# OBCv4_23.net
KiCad netlist of a schematic drawn in EAGLE
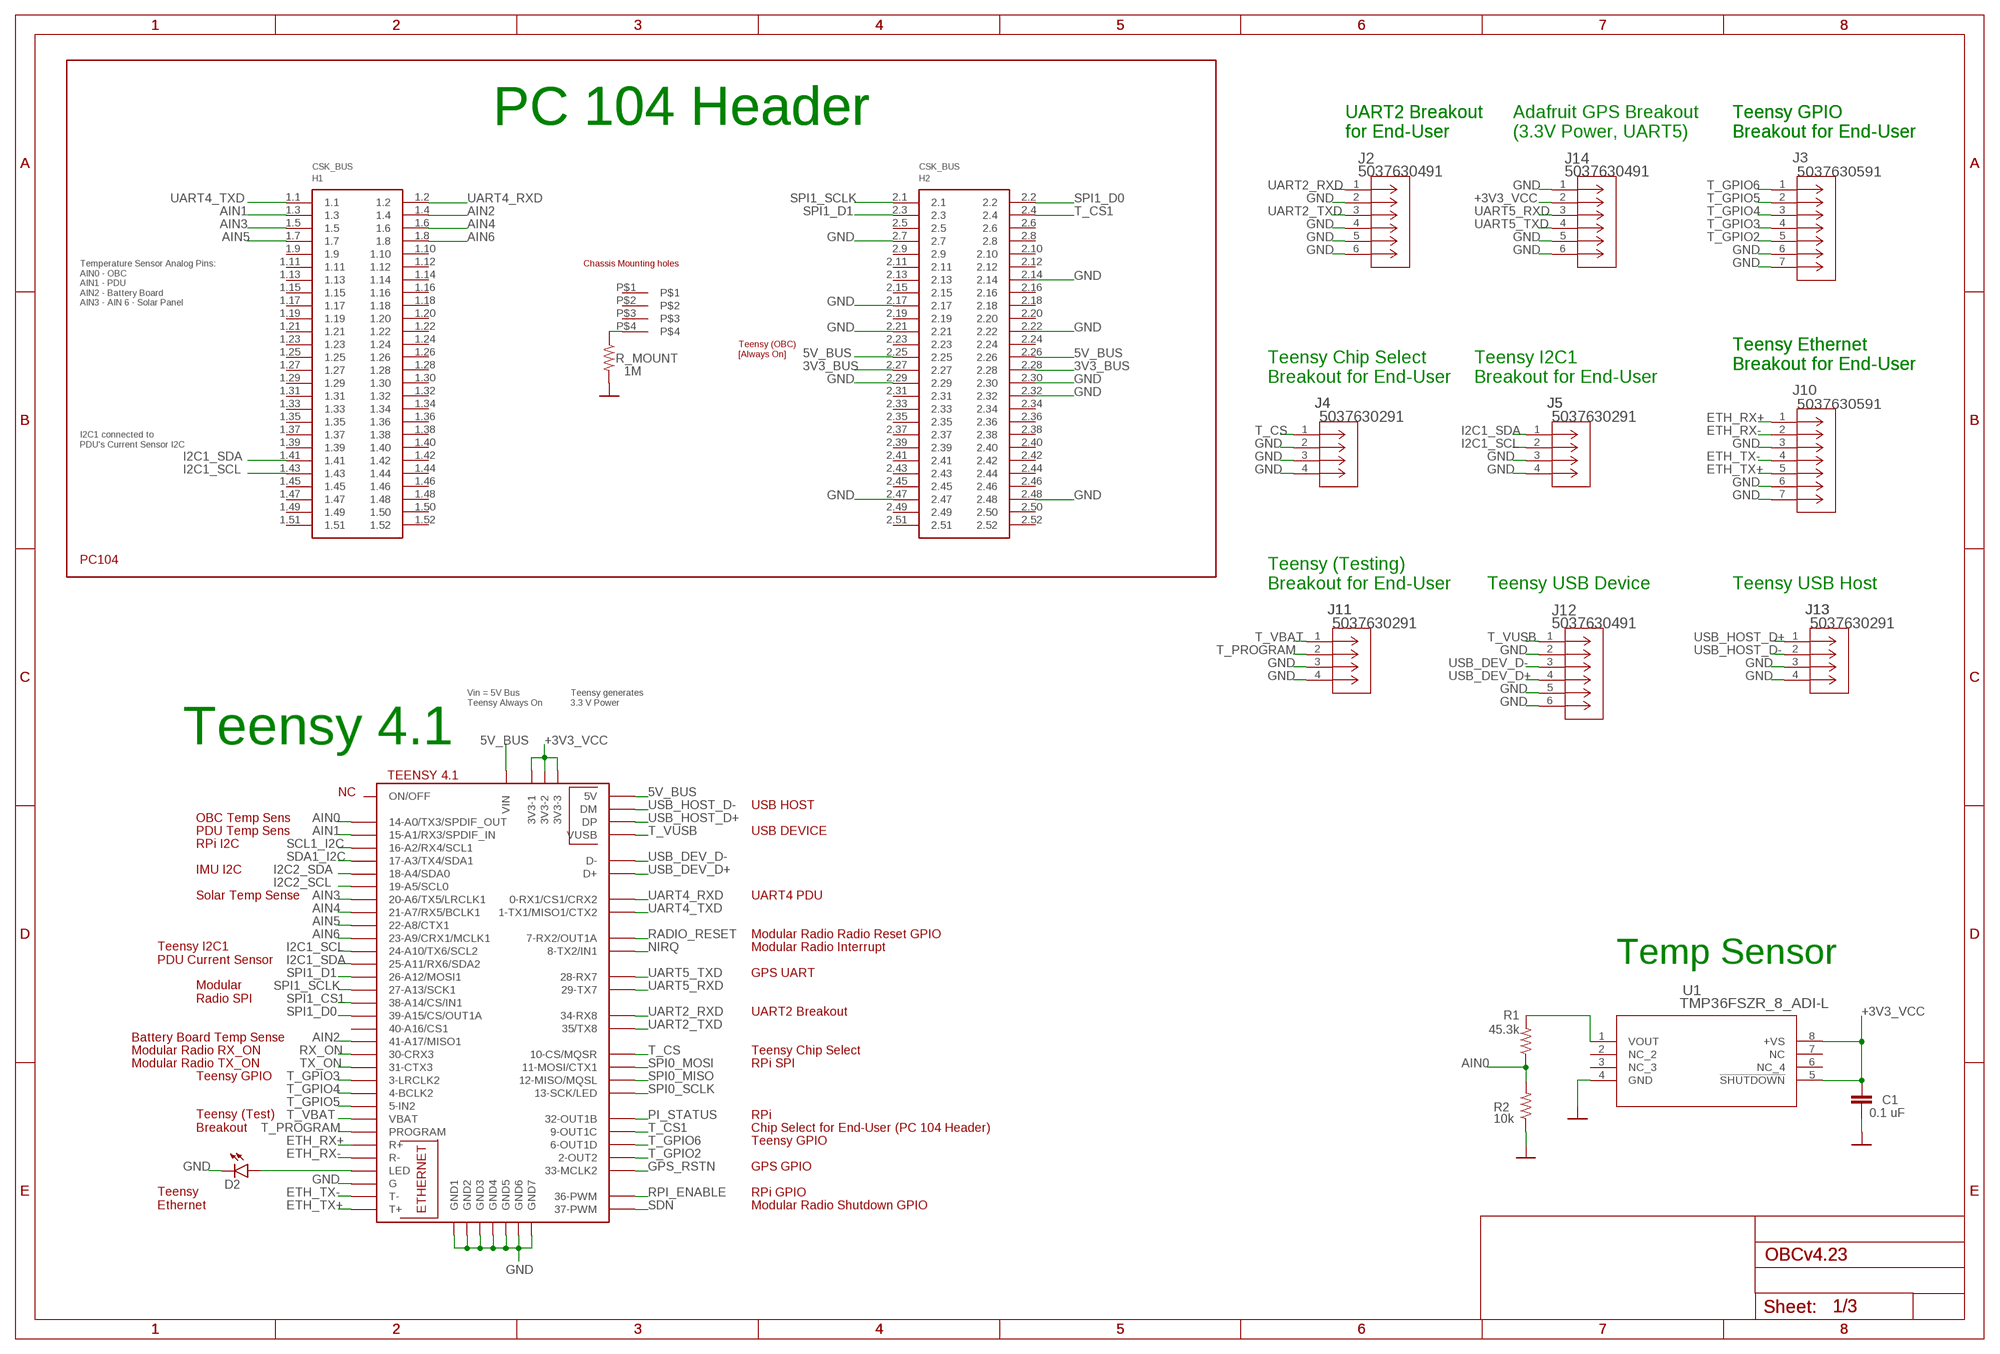
[diagram p0: schematic, sheet 1]
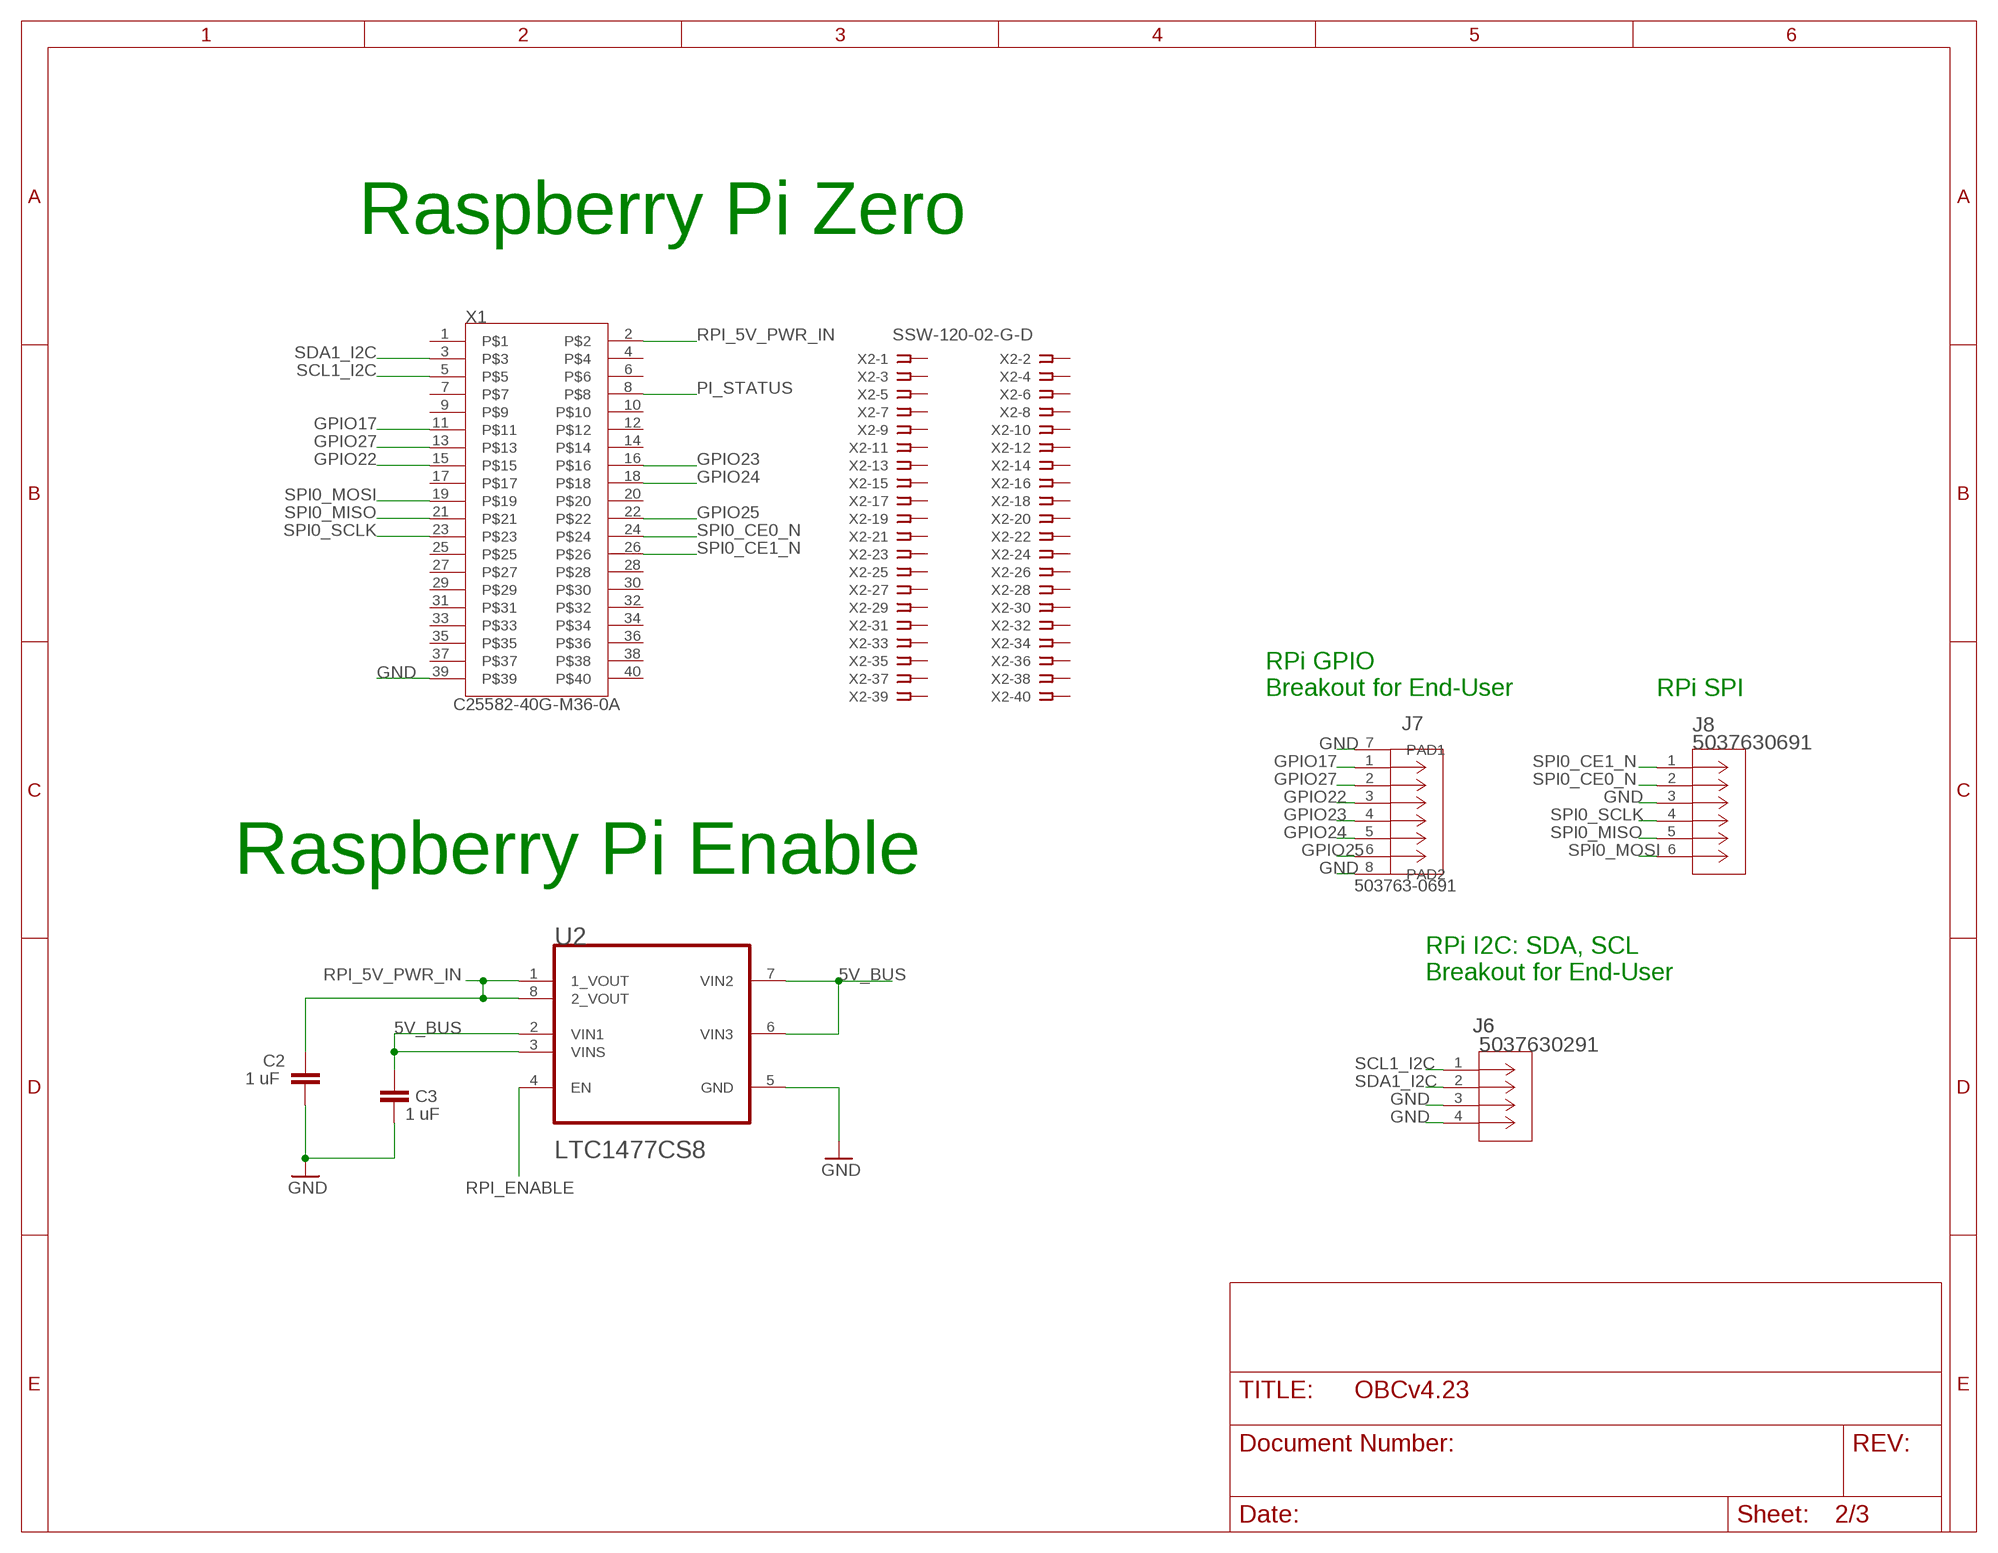
[diagram p1: schematic, sheet 2]
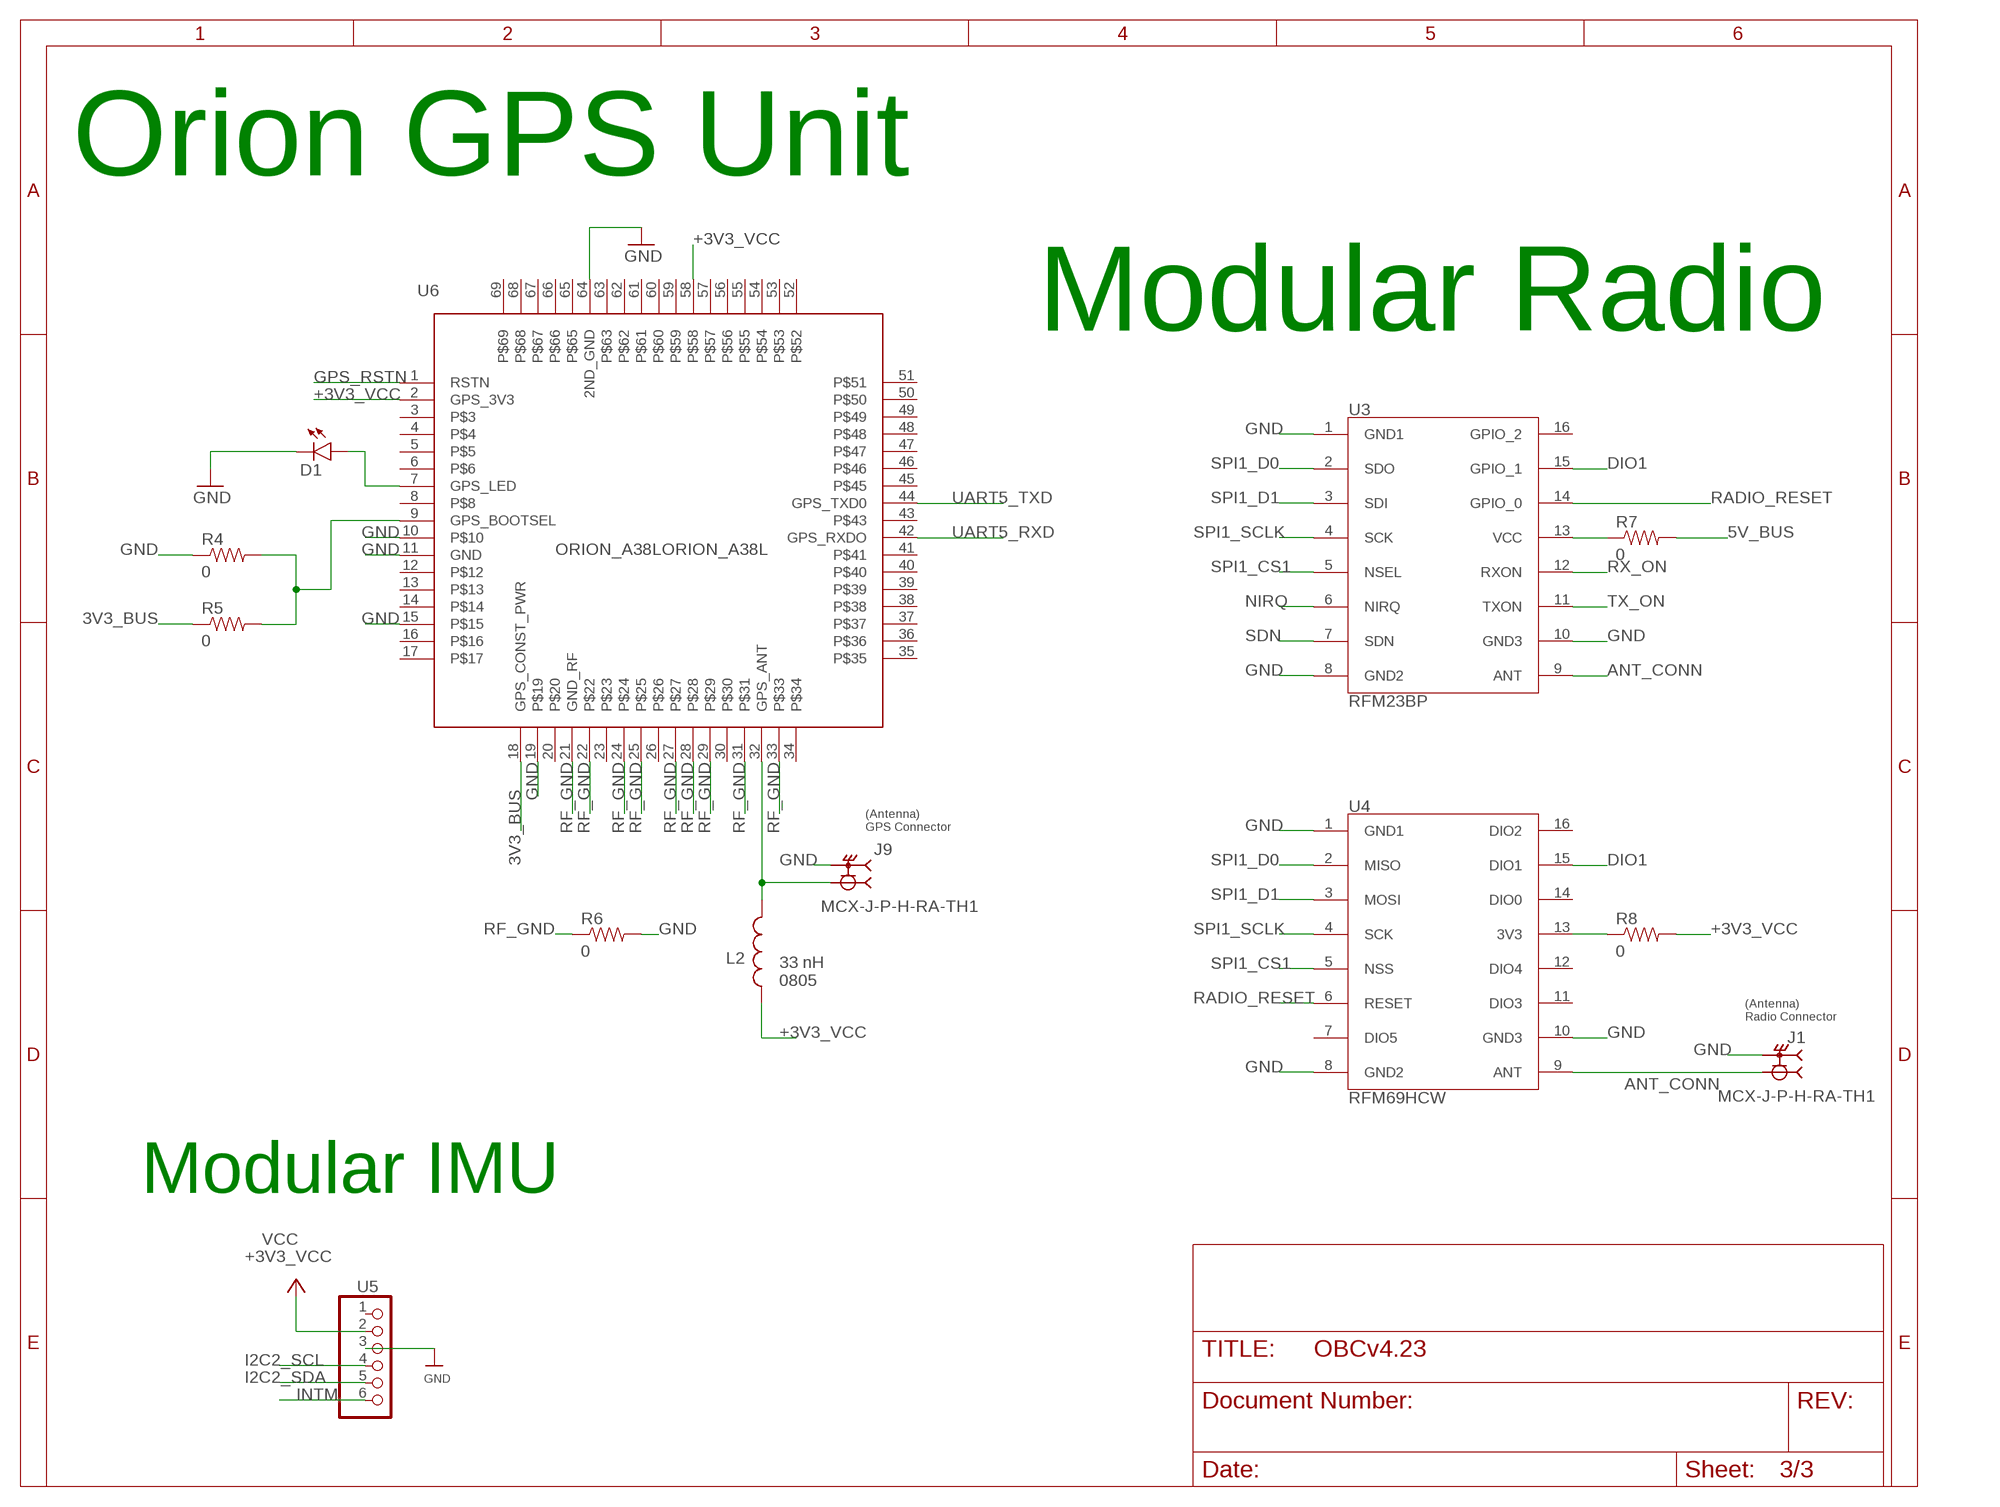
[diagram p2: schematic, sheet 3]

(export (version "E")
  (design (tool "Eeschema 10.0.6"))
  (components
    (comp (ref "D1")
      (value "LEDCHIP-LED0603")
      (footprint "eagle-import:CHIP-LED0603")
      (libsource (lib "eagle-import") (part "LEDCHIP-LED0603"))
    )
    (comp (ref "J1")
      (value "MCX-J-P-H-RA-TH1")
      (footprint "eagle-import:SAMTEC_MCX-J-P-H-RA-TH1")
      (fields (field (name "DIGI-KEY_PART_NUMBER") "SAM10607-ND") (field (name "MF") "Samtec"))
      (libsource (lib "eagle-import") (part "MCX-J-P-H-RA-TH1"))
    )
    (comp (ref "J9")
      (value "MCX-J-P-H-RA-TH1")
      (footprint "eagle-import:SAMTEC_MCX-J-P-H-RA-TH1")
      (fields (field (name "DIGI-KEY_PART_NUMBER") "SAM10607-ND") (field (name "MF") "Samtec"))
      (libsource (lib "eagle-import") (part "MCX-J-P-H-RA-TH1"))
    )
    (comp (ref "L2")
      (value "AIMC-0805-2N2S-T")
      (footprint "eagle-import:INDC2012X105N")
      (fields (field (name "DIGI-KEY_PART_NUMBER") "535-11562-1-ND") (field (name "MF") "Abracon"))
      (libsource (lib "eagle-import") (part "AIMC-0805-2N2S-T"))
    )
    (comp (ref "R4")
      (value "0")
      (footprint "eagle-import:0805")
      (libsource (lib "eagle-import") (part "RESISTOR0805-RES"))
    )
    (comp (ref "R5")
      (value "0")
      (footprint "eagle-import:0805")
      (libsource (lib "eagle-import") (part "RESISTOR0805-RES"))
    )
    (comp (ref "R6")
      (value "0")
      (footprint "eagle-import:0805")
      (libsource (lib "eagle-import") (part "RESISTOR0805-RES"))
    )
    (comp (ref "R7")
      (value "0")
      (footprint "eagle-import:1206")
      (libsource (lib "eagle-import") (part "RESISTOR1206"))
    )
    (comp (ref "R8")
      (value "0")
      (footprint "eagle-import:1206")
      (libsource (lib "eagle-import") (part "RESISTOR1206"))
    )
    (comp (ref "U3")
      (value "RFM23BP")
      (footprint "eagle-import:RFM23BP")
      (libsource (lib "eagle-import") (part "RFM23BP"))
    )
    (comp (ref "U4")
      (value "RFM69HCW")
      (footprint "eagle-import:RFM69HCW")
      (libsource (lib "eagle-import") (part "RFM69HCW"))
    )
    (comp (ref "U5")
      (value "HEADER-1X670MIL")
      (footprint "eagle-import:1X06_ROUND_70")
      (libsource (lib "eagle-import") (part "HEADER-1X670MIL"))
    )
    (comp (ref "U6")
      (value "ORION_A38LORION_A38L")
      (footprint "eagle-import:ORION_A38L")
      (libsource (lib "eagle-import") (part "ORION_A38LORION_A38L"))
    )
    (comp (ref "C1")
      (value "0.1 uF")
      (footprint "eagle-import:0805")
      (libsource (lib "eagle-import") (part "CAP0805"))
    )
    (comp (ref "D2")
      (value "LEDCHIP-LED0603")
      (footprint "eagle-import:CHIP-LED0603")
      (libsource (lib "eagle-import") (part "LEDCHIP-LED0603"))
    )
    (comp (ref "H1")
      (value "PC104_WCONN")
      (footprint "eagle-import:PC104_WCONN")
      (libsource (lib "eagle-import") (part "PC104_WCONN"))
    )
    (comp (ref "J2")
      (value "5037630491")
      (footprint "eagle-import:CON_5037630491")
      (fields (field (name "COPYRIGHT") "Copyright (C) 2018 Accelerated Designs. All rights reserved"))
      (libsource (lib "eagle-import") (part "5037630491"))
    )
    (comp (ref "J3")
      (value "5037630591")
      (footprint "eagle-import:CON_5037630591")
      (fields (field (name "COPYRIGHT") "Copyright (C) 2021 Ultra Librarian. All rights reserved."))
      (libsource (lib "eagle-import") (part "5037630591"))
    )
    (comp (ref "J4")
      (value "5037630291")
      (footprint "eagle-import:CON_5037630291")
      (fields (field (name "COPYRIGHT") "Copyright (C) 2018 Accelerated Designs. All rights reserved"))
      (libsource (lib "eagle-import") (part "5037630291"))
    )
    (comp (ref "J5")
      (value "5037630291")
      (footprint "eagle-import:CON_5037630291")
      (fields (field (name "COPYRIGHT") "Copyright (C) 2018 Accelerated Designs. All rights reserved"))
      (libsource (lib "eagle-import") (part "5037630291"))
    )
    (comp (ref "J10")
      (value "5037630591")
      (footprint "eagle-import:CON_5037630591")
      (fields (field (name "COPYRIGHT") "Copyright (C) 2021 Ultra Librarian. All rights reserved."))
      (libsource (lib "eagle-import") (part "5037630591"))
    )
    (comp (ref "J11")
      (value "5037630291")
      (footprint "eagle-import:CON_5037630291")
      (fields (field (name "COPYRIGHT") "Copyright (C) 2018 Accelerated Designs. All rights reserved"))
      (libsource (lib "eagle-import") (part "5037630291"))
    )
    (comp (ref "J12")
      (value "5037630491")
      (footprint "eagle-import:CON_5037630491")
      (fields (field (name "COPYRIGHT") "Copyright (C) 2018 Accelerated Designs. All rights reserved"))
      (libsource (lib "eagle-import") (part "5037630491"))
    )
    (comp (ref "J13")
      (value "5037630291")
      (footprint "eagle-import:CON_5037630291")
      (fields (field (name "COPYRIGHT") "Copyright (C) 2018 Accelerated Designs. All rights reserved"))
      (libsource (lib "eagle-import") (part "5037630291"))
    )
    (comp (ref "J14")
      (value "5037630491")
      (footprint "eagle-import:CON_5037630491")
      (fields (field (name "COPYRIGHT") "Copyright (C) 2018 Accelerated Designs. All rights reserved"))
      (libsource (lib "eagle-import") (part "5037630491"))
    )
    (comp (ref "R1")
      (value "45.3k")
      (footprint "eagle-import:0805")
      (libsource (lib "eagle-import") (part "RESISTOR0805-RES"))
    )
    (comp (ref "R2")
      (value "10k")
      (footprint "eagle-import:0805")
      (libsource (lib "eagle-import") (part "RESISTOR0805-RES"))
    )
    (comp (ref "R_MOUNT")
      (value "1M")
      (footprint "eagle-import:0805")
      (libsource (lib "eagle-import") (part "RESISTOR0805-RES"))
    )
    (comp (ref "U$1")
      (value "TEENSY41TEENSY")
      (footprint "eagle-import:TEENSY41")
      (libsource (lib "eagle-import") (part "TEENSY41TEENSY"))
    )
    (comp (ref "U1")
      (value "TMP36FSZR_8_ADI-L")
      (footprint "eagle-import:R_8_ADI-L")
      (fields
        (field (name "MANUFACTURER_PART_NUMBER") "TMP36FSZ")
        (field (name "COPYRIGHT") "Copyright (C) 2021 Ultra Librarian. All rights reserved.")
      )
      (libsource (lib "eagle-import") (part "TMP36FSZR_8_ADI-L"))
    )
    (comp (ref "C2")
      (value "1 uF")
      (footprint "eagle-import:0805")
      (libsource (lib "eagle-import") (part "CAP0805"))
    )
    (comp (ref "C3")
      (value "1 uF")
      (footprint "eagle-import:0805")
      (libsource (lib "eagle-import") (part "CAP0805"))
    )
    (comp (ref "J6")
      (value "5037630291")
      (footprint "eagle-import:CON_5037630291")
      (fields (field (name "COPYRIGHT") "Copyright (C) 2018 Accelerated Designs. All rights reserved"))
      (libsource (lib "eagle-import") (part "5037630291"))
    )
    (comp (ref "J7")
      (value "503763-0691")
      (footprint "eagle-import:CONN_503763-0691_MOL")
      (fields (field (name "COPYRIGHT") "Copyright (C) 2018 Accelerated Designs. All rights reserved"))
      (libsource (lib "eagle-import") (part "503763-0691"))
    )
    (comp (ref "J8")
      (value "5037630691")
      (footprint "eagle-import:CONN_503763-0691_MOL")
      (fields
        (field (name "MANUFACTURER_PART_NUMBER") "503763-0691")
        (field (name "COPYRIGHT") "Copyright (C) 2018 Accelerated Designs. All rights reserved")
      )
      (libsource (lib "eagle-import") (part "5037630691"))
    )
    (comp (ref "U2")
      (value "LTC1477CS8LINEAR_TECHNOLOGY_LTC1477CS8_0_2")
      (footprint "eagle-import:LINEAR_TECHNOLOGY_LTC1477CS8_2")
      (fields (field (name "MF") "Linear Technology") (field (name "MPN") "LTC1477CS8"))
      (libsource (lib "eagle-import") (part "LTC1477CS8LINEAR_TECHNOLOGY_LTC1477CS8_0_2"))
    )
    (comp (ref "X1")
      (value "C25582-40G-M36-0A")
      (footprint "eagle-import:ADAFRUIT_C25582-40G-M36-0A_0")
      (libsource (lib "eagle-import") (part "C25582-40G-M36-0A"))
    )
    (comp (ref "X2")
      (value "SSW-120-02-G-D")
      (footprint "eagle-import:SSW-120-02-G-D")
      (fields (field (name "MF") "Samtec Inc."))
      (libsource (lib "eagle-import") (part "SSW-120-02-G-D"))
    )
  )
  (nets
    (net (code "1") (name "+3V3_VCC") (class "Default")
      (node (ref "C1") (pin "1") (pinfunction "1_1") (pintype "passive"))
      (node (ref "J14") (pin "2") (pinfunction "2_2") (pintype "passive"))
      (node (ref "L2") (pin "1") (pinfunction "1_1") (pintype "passive"))
      (node (ref "R8") (pin "2") (pinfunction "2_2") (pintype "passive"))
      (node (ref "U$1") (pin "3V3-1") (pinfunction "3V3-1_3V3-1") (pintype "bidirectional"))
      (node (ref "U$1") (pin "3V3-2") (pinfunction "3V3-2_3V3-2") (pintype "bidirectional"))
      (node (ref "U$1") (pin "3V3-3") (pinfunction "3V3-3_3V3-3") (pintype "bidirectional"))
      (node (ref "U1") (pin "5") (pinfunction "~{SHUTDOWN}_5") (pintype "passive"))
      (node (ref "U1") (pin "8") (pinfunction "+VS_8") (pintype "power_in"))
      (node (ref "U5") (pin "2") (pinfunction "2_2") (pintype "passive"))
      (node (ref "U6") (pin "2") (pinfunction "GPS_3V3_2") (pintype "bidirectional"))
      (node (ref "U6") (pin "58") (pinfunction "P$58_58") (pintype "bidirectional"))
    )
    (net (code "2") (name "3V3_BUS") (class "Default")
      (node (ref "H1") (pin "2.27") (pinfunction "2.27_2.27") (pintype "bidirectional"))
      (node (ref "H1") (pin "2.28") (pinfunction "2.28_2.28") (pintype "bidirectional"))
      (node (ref "R5") (pin "1") (pinfunction "1_1") (pintype "passive"))
      (node (ref "U6") (pin "18") (pinfunction "GPS_CONST_PWR_18") (pintype "bidirectional"))
    )
    (net (code "3") (name "5V_BUS") (class "Default")
      (node (ref "C3") (pin "1") (pinfunction "1_1") (pintype "passive"))
      (node (ref "H1") (pin "2.25") (pinfunction "2.25_2.25") (pintype "bidirectional"))
      (node (ref "H1") (pin "2.26") (pinfunction "2.26_2.26") (pintype "bidirectional"))
      (node (ref "R7") (pin "2") (pinfunction "2_2") (pintype "passive"))
      (node (ref "U$1") (pin "+5V") (pinfunction "5V_+5V") (pintype "bidirectional"))
      (node (ref "U$1") (pin "VIN") (pinfunction "VIN_VIN") (pintype "bidirectional"))
      (node (ref "U2") (pin "2") (pinfunction "VIN1_2") (pintype "power_in"))
      (node (ref "U2") (pin "3") (pinfunction "VINS_3") (pintype "power_in"))
      (node (ref "U2") (pin "6") (pinfunction "VIN3_6") (pintype "power_in"))
      (node (ref "U2") (pin "7") (pinfunction "VIN2_7") (pintype "power_in"))
    )
    (net (code "4") (name "AIN0") (class "Default")
      (node (ref "R1") (pin "1") (pinfunction "1_1") (pintype "passive"))
      (node (ref "R2") (pin "2") (pinfunction "2_2") (pintype "passive"))
      (node (ref "U$1") (pin "14-A0/TX3/SPDIF_OUT") (pinfunction "14-A0/TX3/SPDIF_OUT_14-A0/TX3/SPDIF_OUT") (pintype "bidirectional"))
    )
    (net (code "5") (name "AIN1") (class "Default")
      (node (ref "H1") (pin "1.3") (pinfunction "1.3_1.3") (pintype "bidirectional"))
      (node (ref "U$1") (pin "15-A1/RX3/SPDIF_IN") (pinfunction "15-A1/RX3/SPDIF_IN_15-A1/RX3/SPDIF_IN") (pintype "bidirectional"))
    )
    (net (code "6") (name "AIN2") (class "Default")
      (node (ref "H1") (pin "1.4") (pinfunction "1.4_1.4") (pintype "bidirectional"))
      (node (ref "U$1") (pin "41-A17/MISO1") (pinfunction "41-A17/MISO1_41-A17/MISO1") (pintype "bidirectional"))
    )
    (net (code "7") (name "AIN3") (class "Default")
      (node (ref "H1") (pin "1.5") (pinfunction "1.5_1.5") (pintype "bidirectional"))
      (node (ref "U$1") (pin "20-A6/TX5/LRCLK1") (pinfunction "20-A6/TX5/LRCLK1_20-A6/TX5/LRCLK1") (pintype "bidirectional"))
    )
    (net (code "8") (name "AIN4") (class "Default")
      (node (ref "H1") (pin "1.6") (pinfunction "1.6_1.6") (pintype "bidirectional"))
      (node (ref "U$1") (pin "21-A7/RX5/BCLK1") (pinfunction "21-A7/RX5/BCLK1_21-A7/RX5/BCLK1") (pintype "bidirectional"))
    )
    (net (code "9") (name "AIN5") (class "Default")
      (node (ref "H1") (pin "1.7") (pinfunction "1.7_1.7") (pintype "bidirectional"))
      (node (ref "U$1") (pin "22-A8/CTX1") (pinfunction "22-A8/CTX1_22-A8/CTX1") (pintype "bidirectional"))
    )
    (net (code "10") (name "AIN6") (class "Default")
      (node (ref "H1") (pin "1.8") (pinfunction "1.8_1.8") (pintype "bidirectional"))
      (node (ref "U$1") (pin "23-A9/CRX1/MCLK1") (pinfunction "23-A9/CRX1/MCLK1_23-A9/CRX1/MCLK1") (pintype "bidirectional"))
    )
    (net (code "11") (name "ANT_CONN") (class "Default")
      (node (ref "J1") (pin "1") (pinfunction "1_1") (pintype "passive"))
      (node (ref "U3") (pin "9") (pinfunction "ANT_9") (pintype "bidirectional"))
      (node (ref "U4") (pin "9") (pinfunction "ANT_9") (pintype "bidirectional"))
    )
    (net (code "12") (name "DIO1") (class "Default")
      (node (ref "U3") (pin "15") (pinfunction "GPIO_1_15") (pintype "bidirectional"))
      (node (ref "U4") (pin "15") (pinfunction "DIO1_15") (pintype "bidirectional"))
    )
    (net (code "13") (name "ETH_RX+") (class "Default")
      (node (ref "J10") (pin "1") (pinfunction "1_1") (pintype "passive"))
      (node (ref "U$1") (pin "R+") (pinfunction "R+_R+") (pintype "bidirectional"))
    )
    (net (code "14") (name "ETH_RX-") (class "Default")
      (node (ref "J10") (pin "2") (pinfunction "2_2") (pintype "passive"))
      (node (ref "U$1") (pin "R-") (pinfunction "R-_R-") (pintype "bidirectional"))
    )
    (net (code "15") (name "ETH_TX+") (class "Default")
      (node (ref "J10") (pin "5") (pinfunction "5_5") (pintype "passive"))
      (node (ref "U$1") (pin "T+") (pinfunction "T+_T+") (pintype "bidirectional"))
    )
    (net (code "16") (name "ETH_TX-") (class "Default")
      (node (ref "J10") (pin "4") (pinfunction "4_4") (pintype "passive"))
      (node (ref "U$1") (pin "T-") (pinfunction "T-_T-") (pintype "bidirectional"))
    )
    (net (code "17") (name "GND") (class "Default")
      (node (ref "C1") (pin "2") (pinfunction "2_2") (pintype "passive"))
      (node (ref "C2") (pin "2") (pinfunction "2_2") (pintype "passive"))
      (node (ref "C3") (pin "2") (pinfunction "2_2") (pintype "passive"))
      (node (ref "D1") (pin "C") (pinfunction "C_C") (pintype "passive"))
      (node (ref "D2") (pin "C") (pinfunction "C_C") (pintype "passive"))
      (node (ref "H1") (pin "2.14") (pinfunction "2.14_2.14") (pintype "bidirectional"))
      (node (ref "H1") (pin "2.17") (pinfunction "2.17_2.17") (pintype "bidirectional"))
      (node (ref "H1") (pin "2.21") (pinfunction "2.21_2.21") (pintype "bidirectional"))
      (node (ref "H1") (pin "2.22") (pinfunction "2.22_2.22") (pintype "bidirectional"))
      (node (ref "H1") (pin "2.29") (pinfunction "2.29_2.29") (pintype "bidirectional"))
      (node (ref "H1") (pin "2.30") (pinfunction "2.30_2.30") (pintype "bidirectional"))
      (node (ref "H1") (pin "2.32") (pinfunction "2.32_2.32") (pintype "bidirectional"))
      (node (ref "H1") (pin "2.47") (pinfunction "2.47_2.47") (pintype "bidirectional"))
      (node (ref "H1") (pin "2.48") (pinfunction "2.48_2.48") (pintype "bidirectional"))
      (node (ref "H1") (pin "2.7") (pinfunction "2.7_2.7") (pintype "bidirectional"))
      (node (ref "J1") (pin "S1") (pinfunction "2_S1") (pintype "passive"))
      (node (ref "J1") (pin "S2") (pinfunction "2_S2") (pintype "passive"))
      (node (ref "J1") (pin "S3") (pinfunction "2_S3") (pintype "passive"))
      (node (ref "J1") (pin "S4") (pinfunction "2_S4") (pintype "passive"))
      (node (ref "J10") (pin "3") (pinfunction "3_3") (pintype "passive"))
      (node (ref "J10") (pin "6") (pinfunction "6_6") (pintype "passive"))
      (node (ref "J10") (pin "7") (pinfunction "7_7") (pintype "passive"))
      (node (ref "J11") (pin "3") (pinfunction "3_3") (pintype "passive"))
      (node (ref "J11") (pin "4") (pinfunction "4_4") (pintype "passive"))
      (node (ref "J12") (pin "2") (pinfunction "2_2") (pintype "passive"))
      (node (ref "J12") (pin "5") (pinfunction "5_5") (pintype "passive"))
      (node (ref "J12") (pin "6") (pinfunction "6_6") (pintype "passive"))
      (node (ref "J13") (pin "3") (pinfunction "3_3") (pintype "passive"))
      (node (ref "J13") (pin "4") (pinfunction "4_4") (pintype "passive"))
      (node (ref "J14") (pin "1") (pinfunction "1_1") (pintype "passive"))
      (node (ref "J14") (pin "5") (pinfunction "5_5") (pintype "passive"))
      (node (ref "J14") (pin "6") (pinfunction "6_6") (pintype "passive"))
      (node (ref "J2") (pin "2") (pinfunction "2_2") (pintype "passive"))
      (node (ref "J2") (pin "4") (pinfunction "4_4") (pintype "passive"))
      (node (ref "J2") (pin "5") (pinfunction "5_5") (pintype "passive"))
      (node (ref "J2") (pin "6") (pinfunction "6_6") (pintype "passive"))
      (node (ref "J3") (pin "6") (pinfunction "6_6") (pintype "passive"))
      (node (ref "J3") (pin "7") (pinfunction "7_7") (pintype "passive"))
      (node (ref "J4") (pin "2") (pinfunction "2_2") (pintype "passive"))
      (node (ref "J4") (pin "3") (pinfunction "3_3") (pintype "passive"))
      (node (ref "J4") (pin "4") (pinfunction "4_4") (pintype "passive"))
      (node (ref "J5") (pin "3") (pinfunction "3_3") (pintype "passive"))
      (node (ref "J5") (pin "4") (pinfunction "4_4") (pintype "passive"))
      (node (ref "J6") (pin "3") (pinfunction "3_3") (pintype "passive"))
      (node (ref "J6") (pin "4") (pinfunction "4_4") (pintype "passive"))
      (node (ref "J7") (pin "7") (pinfunction "PAD1_7") (pintype "bidirectional"))
      (node (ref "J7") (pin "8") (pinfunction "PAD2_8") (pintype "bidirectional"))
      (node (ref "J8") (pin "3") (pinfunction "3_3") (pintype "passive"))
      (node (ref "J9") (pin "S1") (pinfunction "2_S1") (pintype "passive"))
      (node (ref "J9") (pin "S2") (pinfunction "2_S2") (pintype "passive"))
      (node (ref "J9") (pin "S3") (pinfunction "2_S3") (pintype "passive"))
      (node (ref "J9") (pin "S4") (pinfunction "2_S4") (pintype "passive"))
      (node (ref "R2") (pin "1") (pinfunction "1_1") (pintype "passive"))
      (node (ref "R4") (pin "1") (pinfunction "1_1") (pintype "passive"))
      (node (ref "R6") (pin "2") (pinfunction "2_2") (pintype "passive"))
      (node (ref "R_MOUNT") (pin "2") (pinfunction "2_2") (pintype "passive"))
      (node (ref "U$1") (pin "G") (pinfunction "G_G") (pintype "bidirectional"))
      (node (ref "U$1") (pin "GND") (pinfunction "GND7_GND") (pintype "bidirectional"))
      (node (ref "U$1") (pin "GND1") (pinfunction "GND1_GND1") (pintype "bidirectional"))
      (node (ref "U$1") (pin "GND2") (pinfunction "GND2_GND2") (pintype "bidirectional"))
      (node (ref "U$1") (pin "GND3") (pinfunction "GND3_GND3") (pintype "bidirectional"))
      (node (ref "U$1") (pin "GND4") (pinfunction "GND4_GND4") (pintype "bidirectional"))
      (node (ref "U$1") (pin "GND5") (pinfunction "GND5_GND5") (pintype "bidirectional"))
      (node (ref "U$1") (pin "GND6") (pinfunction "GND6_GND6") (pintype "bidirectional"))
      (node (ref "U1") (pin "4") (pinfunction "GND_4") (pintype "passive"))
      (node (ref "U2") (pin "5") (pinfunction "GND_5") (pintype "power_in"))
      (node (ref "U3") (pin "1") (pinfunction "GND1_1") (pintype "bidirectional"))
      (node (ref "U3") (pin "10") (pinfunction "GND3_10") (pintype "bidirectional"))
      (node (ref "U3") (pin "8") (pinfunction "GND2_8") (pintype "bidirectional"))
      (node (ref "U4") (pin "1") (pinfunction "GND1_1") (pintype "bidirectional"))
      (node (ref "U4") (pin "10") (pinfunction "GND3_10") (pintype "bidirectional"))
      (node (ref "U4") (pin "8") (pinfunction "GND2_8") (pintype "bidirectional"))
      (node (ref "U5") (pin "3") (pinfunction "3_3") (pintype "passive"))
      (node (ref "U6") (pin "10") (pinfunction "P$10_10") (pintype "bidirectional"))
      (node (ref "U6") (pin "11") (pinfunction "GND_11") (pintype "bidirectional"))
      (node (ref "U6") (pin "15") (pinfunction "P$15_15") (pintype "bidirectional"))
      (node (ref "U6") (pin "19") (pinfunction "P$19_19") (pintype "bidirectional"))
      (node (ref "U6") (pin "64") (pinfunction "2ND_GND_64") (pintype "bidirectional"))
      (node (ref "X1") (pin "39") (pinfunction "P$39_39") (pintype "bidirectional"))
    )
    (net (code "18") (name "GPIO17") (class "Default")
      (node (ref "J7") (pin "1") (pinfunction "1_1") (pintype "passive"))
      (node (ref "X1") (pin "11") (pinfunction "P$11_11") (pintype "bidirectional"))
    )
    (net (code "19") (name "GPIO22") (class "Default")
      (node (ref "J7") (pin "3") (pinfunction "3_3") (pintype "passive"))
      (node (ref "X1") (pin "15") (pinfunction "P$15_15") (pintype "bidirectional"))
    )
    (net (code "20") (name "GPIO23") (class "Default")
      (node (ref "J7") (pin "4") (pinfunction "4_4") (pintype "passive"))
      (node (ref "X1") (pin "16") (pinfunction "P$16_16") (pintype "bidirectional"))
    )
    (net (code "21") (name "GPIO24") (class "Default")
      (node (ref "J7") (pin "5") (pinfunction "5_5") (pintype "passive"))
      (node (ref "X1") (pin "18") (pinfunction "P$18_18") (pintype "bidirectional"))
    )
    (net (code "22") (name "GPIO25") (class "Default")
      (node (ref "J7") (pin "6") (pinfunction "6_6") (pintype "passive"))
      (node (ref "X1") (pin "22") (pinfunction "P$22_22") (pintype "bidirectional"))
    )
    (net (code "23") (name "GPIO27") (class "Default")
      (node (ref "J7") (pin "2") (pinfunction "2_2") (pintype "passive"))
      (node (ref "X1") (pin "13") (pinfunction "P$13_13") (pintype "bidirectional"))
    )
    (net (code "24") (name "GPS_RSTN") (class "Default")
      (node (ref "U$1") (pin "33-MCLK2") (pinfunction "33-MCLK2_33-MCLK2") (pintype "bidirectional"))
      (node (ref "U6") (pin "1") (pinfunction "RSTN_1") (pintype "bidirectional"))
    )
    (net (code "25") (name "I2C1_SCL") (class "Default")
      (node (ref "H1") (pin "1.43") (pinfunction "1.43_1.43") (pintype "bidirectional"))
      (node (ref "J5") (pin "2") (pinfunction "2_2") (pintype "passive"))
      (node (ref "U$1") (pin "24-A10/TX6/SCL2") (pinfunction "24-A10/TX6/SCL2_24-A10/TX6/SCL2") (pintype "bidirectional"))
    )
    (net (code "26") (name "I2C1_SDA") (class "Default")
      (node (ref "H1") (pin "1.41") (pinfunction "1.41_1.41") (pintype "bidirectional"))
      (node (ref "J5") (pin "1") (pinfunction "1_1") (pintype "passive"))
      (node (ref "U$1") (pin "25-A11/RX6/SDA2") (pinfunction "25-A11/RX6/SDA2_25-A11/RX6/SDA2") (pintype "bidirectional"))
    )
    (net (code "27") (name "I2C2_SCL") (class "Default")
      (node (ref "U$1") (pin "19-A5/SCL0") (pinfunction "19-A5/SCL0_19-A5/SCL0") (pintype "bidirectional"))
      (node (ref "U5") (pin "4") (pinfunction "4_4") (pintype "passive"))
    )
    (net (code "28") (name "I2C2_SDA") (class "Default")
      (node (ref "U$1") (pin "18-A4/SDA0") (pinfunction "18-A4/SDA0_18-A4/SDA0") (pintype "bidirectional"))
      (node (ref "U5") (pin "5") (pinfunction "5_5") (pintype "passive"))
    )
    (net (code "29") (name "INTM") (class "Default")
      (node (ref "U5") (pin "6") (pinfunction "6_6") (pintype "passive"))
    )
    (net (code "30") (name "NIRQ") (class "Default")
      (node (ref "U$1") (pin "8-TX2/IN1") (pinfunction "8-TX2/IN1_8-TX2/IN1") (pintype "bidirectional"))
      (node (ref "U3") (pin "6") (pinfunction "NIRQ_6") (pintype "bidirectional"))
    )
    (net (code "31") (name "Net-(D2-PadA)") (class "Default")
      (node (ref "D2") (pin "A") (pinfunction "A_A") (pintype "passive"))
      (node (ref "U$1") (pin "LED") (pinfunction "LED_LED") (pintype "bidirectional"))
    )
    (net (code "32") (name "Net-(H1-PadP$4)") (class "Default")
      (node (ref "H1") (pin "P$4") (pinfunction "P$4_P$4") (pintype "bidirectional"))
      (node (ref "R_MOUNT") (pin "1") (pinfunction "1_1") (pintype "passive"))
    )
    (net (code "33") (name "Net-(U1-VOUT)") (class "Default")
      (node (ref "R1") (pin "2") (pinfunction "2_2") (pintype "passive"))
      (node (ref "U1") (pin "1") (pinfunction "VOUT_1") (pintype "output"))
    )
    (net (code "34") (name "Net-(U3-VCC)") (class "Default")
      (node (ref "R7") (pin "1") (pinfunction "1_1") (pintype "passive"))
      (node (ref "U3") (pin "13") (pinfunction "VCC_13") (pintype "bidirectional"))
    )
    (net (code "35") (name "Net-(U4-3V3)") (class "Default")
      (node (ref "R8") (pin "1") (pinfunction "1_1") (pintype "passive"))
      (node (ref "U4") (pin "13") (pinfunction "3V3_13") (pintype "bidirectional"))
    )
    (net (code "36") (name "Net-(U6-GPS_ANT)") (class "Default")
      (node (ref "J9") (pin "1") (pinfunction "1_1") (pintype "passive"))
      (node (ref "L2") (pin "2") (pinfunction "2_2") (pintype "passive"))
      (node (ref "U6") (pin "32") (pinfunction "GPS_ANT_32") (pintype "bidirectional"))
    )
    (net (code "37") (name "Net-(U6-GPS_BOOTSEL)") (class "Default")
      (node (ref "R4") (pin "2") (pinfunction "2_2") (pintype "passive"))
      (node (ref "R5") (pin "2") (pinfunction "2_2") (pintype "passive"))
      (node (ref "U6") (pin "9") (pinfunction "GPS_BOOTSEL_9") (pintype "bidirectional"))
    )
    (net (code "38") (name "Net-(U6-GPS_LED)") (class "Default")
      (node (ref "D1") (pin "A") (pinfunction "A_A") (pintype "passive"))
      (node (ref "U6") (pin "7") (pinfunction "GPS_LED_7") (pintype "bidirectional"))
    )
    (net (code "39") (name "PI_STATUS") (class "Default")
      (node (ref "U$1") (pin "32-OUT1B") (pinfunction "32-OUT1B_32-OUT1B") (pintype "bidirectional"))
      (node (ref "X1") (pin "8") (pinfunction "P$8_8") (pintype "bidirectional"))
    )
    (net (code "40") (name "RADIO_RESET") (class "Default")
      (node (ref "U$1") (pin "7-RX2/OUT1A") (pinfunction "7-RX2/OUT1A_7-RX2/OUT1A") (pintype "bidirectional"))
      (node (ref "U3") (pin "14") (pinfunction "GPIO_0_14") (pintype "bidirectional"))
      (node (ref "U4") (pin "6") (pinfunction "RESET_6") (pintype "bidirectional"))
    )
    (net (code "41") (name "RF_GND") (class "Default")
      (node (ref "R6") (pin "1") (pinfunction "1_1") (pintype "passive"))
      (node (ref "U6") (pin "21") (pinfunction "GND_RF_21") (pintype "bidirectional"))
      (node (ref "U6") (pin "22") (pinfunction "P$22_22") (pintype "bidirectional"))
      (node (ref "U6") (pin "24") (pinfunction "P$24_24") (pintype "bidirectional"))
      (node (ref "U6") (pin "25") (pinfunction "P$25_25") (pintype "bidirectional"))
      (node (ref "U6") (pin "27") (pinfunction "P$27_27") (pintype "bidirectional"))
      (node (ref "U6") (pin "28") (pinfunction "P$28_28") (pintype "bidirectional"))
      (node (ref "U6") (pin "29") (pinfunction "P$29_29") (pintype "bidirectional"))
      (node (ref "U6") (pin "31") (pinfunction "P$31_31") (pintype "bidirectional"))
      (node (ref "U6") (pin "33") (pinfunction "P$33_33") (pintype "bidirectional"))
    )
    (net (code "42") (name "RPI_5V_PWR_IN") (class "Default")
      (node (ref "C2") (pin "1") (pinfunction "1_1") (pintype "passive"))
      (node (ref "U2") (pin "1") (pinfunction "1_VOUT_1") (pintype "power_in"))
      (node (ref "U2") (pin "8") (pinfunction "2_VOUT_8") (pintype "power_in"))
      (node (ref "X1") (pin "2") (pinfunction "P$2_2") (pintype "bidirectional"))
    )
    (net (code "43") (name "RPI_ENABLE") (class "Default")
      (node (ref "U$1") (pin "36-PWM") (pinfunction "36-PWM_36-PWM") (pintype "bidirectional"))
      (node (ref "U2") (pin "4") (pinfunction "EN_4") (pintype "input"))
    )
    (net (code "44") (name "RX_ON") (class "Default")
      (node (ref "U$1") (pin "30-CRX3") (pinfunction "30-CRX3_30-CRX3") (pintype "bidirectional"))
      (node (ref "U3") (pin "12") (pinfunction "RXON_12") (pintype "bidirectional"))
    )
    (net (code "45") (name "SCL1_I2C") (class "Default")
      (node (ref "J6") (pin "1") (pinfunction "1_1") (pintype "passive"))
      (node (ref "U$1") (pin "16-A2/RX4/SCL1") (pinfunction "16-A2/RX4/SCL1_16-A2/RX4/SCL1") (pintype "bidirectional"))
      (node (ref "X1") (pin "5") (pinfunction "P$5_5") (pintype "bidirectional"))
    )
    (net (code "46") (name "SDA1_I2C") (class "Default")
      (node (ref "J6") (pin "2") (pinfunction "2_2") (pintype "passive"))
      (node (ref "U$1") (pin "17-A3/TX4/SDA1") (pinfunction "17-A3/TX4/SDA1_17-A3/TX4/SDA1") (pintype "bidirectional"))
      (node (ref "X1") (pin "3") (pinfunction "P$3_3") (pintype "bidirectional"))
    )
    (net (code "47") (name "SDN") (class "Default")
      (node (ref "U$1") (pin "37-PWM") (pinfunction "37-PWM_37-PWM") (pintype "bidirectional"))
      (node (ref "U3") (pin "7") (pinfunction "SDN_7") (pintype "bidirectional"))
    )
    (net (code "48") (name "SPI0_CE0_N") (class "Default")
      (node (ref "J8") (pin "2") (pinfunction "2_2") (pintype "passive"))
      (node (ref "X1") (pin "24") (pinfunction "P$24_24") (pintype "bidirectional"))
    )
    (net (code "49") (name "SPI0_CE1_N") (class "Default")
      (node (ref "J8") (pin "1") (pinfunction "1_1") (pintype "passive"))
      (node (ref "X1") (pin "26") (pinfunction "P$26_26") (pintype "bidirectional"))
    )
    (net (code "50") (name "SPI0_MISO") (class "Default")
      (node (ref "J8") (pin "5") (pinfunction "5_5") (pintype "passive"))
      (node (ref "U$1") (pin "12-MISO/MQSL") (pinfunction "12-MISO/MQSL_12-MISO/MQSL") (pintype "bidirectional"))
      (node (ref "X1") (pin "21") (pinfunction "P$21_21") (pintype "bidirectional"))
    )
    (net (code "51") (name "SPI0_MOSI") (class "Default")
      (node (ref "J8") (pin "6") (pinfunction "6_6") (pintype "passive"))
      (node (ref "U$1") (pin "11-MOSI/CTX1") (pinfunction "11-MOSI/CTX1_11-MOSI/CTX1") (pintype "bidirectional"))
      (node (ref "X1") (pin "19") (pinfunction "P$19_19") (pintype "bidirectional"))
    )
    (net (code "52") (name "SPI0_SCLK") (class "Default")
      (node (ref "J8") (pin "4") (pinfunction "4_4") (pintype "passive"))
      (node (ref "U$1") (pin "13-SCK/LED") (pinfunction "13-SCK/LED_13-SCK/LED") (pintype "bidirectional"))
      (node (ref "X1") (pin "23") (pinfunction "P$23_23") (pintype "bidirectional"))
    )
    (net (code "53") (name "SPI1_CS1") (class "Default")
      (node (ref "U$1") (pin "38-A14/CS/IN1") (pinfunction "38-A14/CS/IN1_38-A14/CS/IN1") (pintype "bidirectional"))
      (node (ref "U3") (pin "5") (pinfunction "NSEL_5") (pintype "bidirectional"))
      (node (ref "U4") (pin "5") (pinfunction "NSS_5") (pintype "bidirectional"))
    )
    (net (code "54") (name "SPI1_D0") (class "Default")
      (node (ref "H1") (pin "2.2") (pinfunction "2.2_2.2") (pintype "bidirectional"))
      (node (ref "U$1") (pin "39-A15/CS/OUT1A") (pinfunction "39-A15/CS/OUT1A_39-A15/CS/OUT1A") (pintype "bidirectional"))
      (node (ref "U3") (pin "2") (pinfunction "SDO_2") (pintype "bidirectional"))
      (node (ref "U4") (pin "2") (pinfunction "MISO_2") (pintype "bidirectional"))
    )
    (net (code "55") (name "SPI1_D1") (class "Default")
      (node (ref "H1") (pin "2.3") (pinfunction "2.3_2.3") (pintype "bidirectional"))
      (node (ref "U$1") (pin "26-A12/MOSI1") (pinfunction "26-A12/MOSI1_26-A12/MOSI1") (pintype "bidirectional"))
      (node (ref "U3") (pin "3") (pinfunction "SDI_3") (pintype "bidirectional"))
      (node (ref "U4") (pin "3") (pinfunction "MOSI_3") (pintype "bidirectional"))
    )
    (net (code "56") (name "SPI1_SCLK") (class "Default")
      (node (ref "H1") (pin "2.1") (pinfunction "2.1_2.1") (pintype "bidirectional"))
      (node (ref "U$1") (pin "27-A13/SCK1") (pinfunction "27-A13/SCK1_27-A13/SCK1") (pintype "bidirectional"))
      (node (ref "U3") (pin "4") (pinfunction "SCK_4") (pintype "bidirectional"))
      (node (ref "U4") (pin "4") (pinfunction "SCK_4") (pintype "bidirectional"))
    )
    (net (code "57") (name "TX_ON") (class "Default")
      (node (ref "U$1") (pin "31-CTX3") (pinfunction "31-CTX3_31-CTX3") (pintype "bidirectional"))
      (node (ref "U3") (pin "11") (pinfunction "TXON_11") (pintype "bidirectional"))
    )
    (net (code "58") (name "T_CS") (class "Default")
      (node (ref "J4") (pin "1") (pinfunction "1_1") (pintype "passive"))
      (node (ref "U$1") (pin "10-CS\\MQSR") (pinfunction "10-CS/MQSR_10-CS\\MQSR") (pintype "bidirectional"))
    )
    (net (code "59") (name "T_CS1") (class "Default")
      (node (ref "H1") (pin "2.4") (pinfunction "2.4_2.4") (pintype "bidirectional"))
      (node (ref "U$1") (pin "9-OUT1C") (pinfunction "9-OUT1C_9-OUT1C") (pintype "bidirectional"))
    )
    (net (code "60") (name "T_GPIO2") (class "Default")
      (node (ref "J3") (pin "5") (pinfunction "5_5") (pintype "passive"))
      (node (ref "U$1") (pin "2-OUT2") (pinfunction "2-OUT2_2-OUT2") (pintype "bidirectional"))
    )
    (net (code "61") (name "T_GPIO3") (class "Default")
      (node (ref "J3") (pin "4") (pinfunction "4_4") (pintype "passive"))
      (node (ref "U$1") (pin "3-LRCLK2") (pinfunction "3-LRCLK2_3-LRCLK2") (pintype "bidirectional"))
    )
    (net (code "62") (name "T_GPIO4") (class "Default")
      (node (ref "J3") (pin "3") (pinfunction "3_3") (pintype "passive"))
      (node (ref "U$1") (pin "4-BCLK2") (pinfunction "4-BCLK2_4-BCLK2") (pintype "bidirectional"))
    )
    (net (code "63") (name "T_GPIO5") (class "Default")
      (node (ref "J3") (pin "2") (pinfunction "2_2") (pintype "passive"))
      (node (ref "U$1") (pin "5-IN2") (pinfunction "5-IN2_5-IN2") (pintype "bidirectional"))
    )
    (net (code "64") (name "T_GPIO6") (class "Default")
      (node (ref "J3") (pin "1") (pinfunction "1_1") (pintype "passive"))
      (node (ref "U$1") (pin "6-OUT1D") (pinfunction "6-OUT1D_6-OUT1D") (pintype "bidirectional"))
    )
    (net (code "65") (name "T_PROGRAM") (class "Default")
      (node (ref "J11") (pin "2") (pinfunction "2_2") (pintype "passive"))
      (node (ref "U$1") (pin "PROGRAM") (pinfunction "PROGRAM_PROGRAM") (pintype "bidirectional"))
    )
    (net (code "66") (name "T_VBAT") (class "Default")
      (node (ref "J11") (pin "1") (pinfunction "1_1") (pintype "passive"))
      (node (ref "U$1") (pin "VBAT") (pinfunction "VBAT_VBAT") (pintype "bidirectional"))
    )
    (net (code "67") (name "T_VUSB") (class "Default")
      (node (ref "J12") (pin "1") (pinfunction "1_1") (pintype "passive"))
      (node (ref "U$1") (pin "VUSB") (pinfunction "VUSB_VUSB") (pintype "bidirectional"))
    )
    (net (code "68") (name "UART2_RXD") (class "Default")
      (node (ref "J2") (pin "1") (pinfunction "1_1") (pintype "passive"))
      (node (ref "U$1") (pin "34-RX8") (pinfunction "34-RX8_34-RX8") (pintype "bidirectional"))
    )
    (net (code "69") (name "UART2_TXD") (class "Default")
      (node (ref "J2") (pin "3") (pinfunction "3_3") (pintype "passive"))
      (node (ref "U$1") (pin "35-TX8") (pinfunction "35/TX8_35-TX8") (pintype "bidirectional"))
    )
    (net (code "70") (name "UART4_RXD") (class "Default")
      (node (ref "H1") (pin "1.2") (pinfunction "1.2_1.2") (pintype "bidirectional"))
      (node (ref "U$1") (pin "0-RX1/CS1/CRX2") (pinfunction "0-RX1/CS1/CRX2_0-RX1/CS1/CRX2") (pintype "bidirectional"))
    )
    (net (code "71") (name "UART4_TXD") (class "Default")
      (node (ref "H1") (pin "1.1") (pinfunction "1.1_1.1") (pintype "bidirectional"))
      (node (ref "U$1") (pin "1-TX1/MISO1/CTX2") (pinfunction "1-TX1/MISO1/CTX2_1-TX1/MISO1/CTX2") (pintype "bidirectional"))
    )
    (net (code "72") (name "UART5_RXD") (class "Default")
      (node (ref "J14") (pin "3") (pinfunction "3_3") (pintype "passive"))
      (node (ref "U$1") (pin "29-TX7") (pinfunction "29-TX7_29-TX7") (pintype "bidirectional"))
      (node (ref "U6") (pin "42") (pinfunction "GPS_RXDO_42") (pintype "input"))
    )
    (net (code "73") (name "UART5_TXD") (class "Default")
      (node (ref "J14") (pin "4") (pinfunction "4_4") (pintype "passive"))
      (node (ref "U$1") (pin "28-RX7") (pinfunction "28-RX7_28-RX7") (pintype "bidirectional"))
      (node (ref "U6") (pin "44") (pinfunction "GPS_TXD0_44") (pintype "output"))
    )
    (net (code "74") (name "USB_DEV_D+") (class "Default")
      (node (ref "J12") (pin "4") (pinfunction "4_4") (pintype "passive"))
      (node (ref "U$1") (pin "D+") (pinfunction "D+_D+") (pintype "bidirectional"))
    )
    (net (code "75") (name "USB_DEV_D-") (class "Default")
      (node (ref "J12") (pin "3") (pinfunction "3_3") (pintype "passive"))
      (node (ref "U$1") (pin "D-") (pinfunction "D-_D-") (pintype "bidirectional"))
    )
    (net (code "76") (name "USB_HOST_D+") (class "Default")
      (node (ref "J13") (pin "1") (pinfunction "1_1") (pintype "passive"))
      (node (ref "U$1") (pin "DP") (pinfunction "DP_DP") (pintype "bidirectional"))
    )
    (net (code "77") (name "USB_HOST_D-") (class "Default")
      (node (ref "J13") (pin "2") (pinfunction "2_2") (pintype "passive"))
      (node (ref "U$1") (pin "DM") (pinfunction "DM_DM") (pintype "bidirectional"))
    )
    (net (code "78") (name "unconnected-(H1-Pad1.9)") (class "Default")
      (node (ref "H1") (pin "1.9") (pinfunction "1.9_1.9") (pintype "bidirectional"))
    )
    (net (code "79") (name "unconnected-(H1-Pad1.10)") (class "Default")
      (node (ref "H1") (pin "1.10") (pinfunction "1.10_1.10") (pintype "bidirectional"))
    )
    (net (code "80") (name "unconnected-(H1-Pad1.11)") (class "Default")
      (node (ref "H1") (pin "1.11") (pinfunction "1.11_1.11") (pintype "bidirectional"))
    )
    (net (code "81") (name "unconnected-(H1-Pad1.12)") (class "Default")
      (node (ref "H1") (pin "1.12") (pinfunction "1.12_1.12") (pintype "bidirectional"))
    )
    (net (code "82") (name "unconnected-(H1-Pad1.13)") (class "Default")
      (node (ref "H1") (pin "1.13") (pinfunction "1.13_1.13") (pintype "bidirectional"))
    )
    (net (code "83") (name "unconnected-(H1-Pad1.14)") (class "Default")
      (node (ref "H1") (pin "1.14") (pinfunction "1.14_1.14") (pintype "bidirectional"))
    )
    (net (code "84") (name "unconnected-(H1-Pad1.15)") (class "Default")
      (node (ref "H1") (pin "1.15") (pinfunction "1.15_1.15") (pintype "bidirectional"))
    )
    (net (code "85") (name "unconnected-(H1-Pad1.16)") (class "Default")
      (node (ref "H1") (pin "1.16") (pinfunction "1.16_1.16") (pintype "bidirectional"))
    )
    (net (code "86") (name "unconnected-(H1-Pad1.17)") (class "Default")
      (node (ref "H1") (pin "1.17") (pinfunction "1.17_1.17") (pintype "bidirectional"))
    )
    (net (code "87") (name "unconnected-(H1-Pad1.18)") (class "Default")
      (node (ref "H1") (pin "1.18") (pinfunction "1.18_1.18") (pintype "bidirectional"))
    )
    (net (code "88") (name "unconnected-(H1-Pad1.19)") (class "Default")
      (node (ref "H1") (pin "1.19") (pinfunction "1.19_1.19") (pintype "bidirectional"))
    )
    (net (code "89") (name "unconnected-(H1-Pad1.20)") (class "Default")
      (node (ref "H1") (pin "1.20") (pinfunction "1.20_1.20") (pintype "bidirectional"))
    )
    (net (code "90") (name "unconnected-(H1-Pad1.21)") (class "Default")
      (node (ref "H1") (pin "1.21") (pinfunction "1.21_1.21") (pintype "bidirectional"))
    )
    (net (code "91") (name "unconnected-(H1-Pad1.22)") (class "Default")
      (node (ref "H1") (pin "1.22") (pinfunction "1.22_1.22") (pintype "bidirectional"))
    )
    (net (code "92") (name "unconnected-(H1-Pad1.23)") (class "Default")
      (node (ref "H1") (pin "1.23") (pinfunction "1.23_1.23") (pintype "bidirectional"))
    )
    (net (code "93") (name "unconnected-(H1-Pad1.24)") (class "Default")
      (node (ref "H1") (pin "1.24") (pinfunction "1.24_1.24") (pintype "bidirectional"))
    )
    (net (code "94") (name "unconnected-(H1-Pad1.25)") (class "Default")
      (node (ref "H1") (pin "1.25") (pinfunction "1.25_1.25") (pintype "bidirectional"))
    )
    (net (code "95") (name "unconnected-(H1-Pad1.26)") (class "Default")
      (node (ref "H1") (pin "1.26") (pinfunction "1.26_1.26") (pintype "bidirectional"))
    )
    (net (code "96") (name "unconnected-(H1-Pad1.27)") (class "Default")
      (node (ref "H1") (pin "1.27") (pinfunction "1.27_1.27") (pintype "bidirectional"))
    )
    (net (code "97") (name "unconnected-(H1-Pad1.28)") (class "Default")
      (node (ref "H1") (pin "1.28") (pinfunction "1.28_1.28") (pintype "bidirectional"))
    )
    (net (code "98") (name "unconnected-(H1-Pad1.29)") (class "Default")
      (node (ref "H1") (pin "1.29") (pinfunction "1.29_1.29") (pintype "bidirectional"))
    )
    (net (code "99") (name "unconnected-(H1-Pad1.30)") (class "Default")
      (node (ref "H1") (pin "1.30") (pinfunction "1.30_1.30") (pintype "bidirectional"))
    )
    (net (code "100") (name "unconnected-(H1-Pad1.31)") (class "Default")
      (node (ref "H1") (pin "1.31") (pinfunction "1.31_1.31") (pintype "bidirectional"))
    )
    (net (code "101") (name "unconnected-(H1-Pad1.32)") (class "Default")
      (node (ref "H1") (pin "1.32") (pinfunction "1.32_1.32") (pintype "bidirectional"))
    )
    (net (code "102") (name "unconnected-(H1-Pad1.33)") (class "Default")
      (node (ref "H1") (pin "1.33") (pinfunction "1.33_1.33") (pintype "bidirectional"))
    )
    (net (code "103") (name "unconnected-(H1-Pad1.34)") (class "Default")
      (node (ref "H1") (pin "1.34") (pinfunction "1.34_1.34") (pintype "bidirectional"))
    )
    (net (code "104") (name "unconnected-(H1-Pad1.35)") (class "Default")
      (node (ref "H1") (pin "1.35") (pinfunction "1.35_1.35") (pintype "bidirectional"))
    )
    (net (code "105") (name "unconnected-(H1-Pad1.36)") (class "Default")
      (node (ref "H1") (pin "1.36") (pinfunction "1.36_1.36") (pintype "bidirectional"))
    )
    (net (code "106") (name "unconnected-(H1-Pad1.37)") (class "Default")
      (node (ref "H1") (pin "1.37") (pinfunction "1.37_1.37") (pintype "bidirectional"))
    )
    (net (code "107") (name "unconnected-(H1-Pad1.38)") (class "Default")
      (node (ref "H1") (pin "1.38") (pinfunction "1.38_1.38") (pintype "bidirectional"))
    )
    (net (code "108") (name "unconnected-(H1-Pad1.39)") (class "Default")
      (node (ref "H1") (pin "1.39") (pinfunction "1.39_1.39") (pintype "bidirectional"))
    )
    (net (code "109") (name "unconnected-(H1-Pad1.40)") (class "Default")
      (node (ref "H1") (pin "1.40") (pinfunction "1.40_1.40") (pintype "bidirectional"))
    )
    (net (code "110") (name "unconnected-(H1-Pad1.42)") (class "Default")
      (node (ref "H1") (pin "1.42") (pinfunction "1.42_1.42") (pintype "bidirectional"))
    )
    (net (code "111") (name "unconnected-(H1-Pad1.44)") (class "Default")
      (node (ref "H1") (pin "1.44") (pinfunction "1.44_1.44") (pintype "bidirectional"))
    )
    (net (code "112") (name "unconnected-(H1-Pad1.45)") (class "Default")
      (node (ref "H1") (pin "1.45") (pinfunction "1.45_1.45") (pintype "bidirectional"))
    )
    (net (code "113") (name "unconnected-(H1-Pad1.46)") (class "Default")
      (node (ref "H1") (pin "1.46") (pinfunction "1.46_1.46") (pintype "bidirectional"))
    )
    (net (code "114") (name "unconnected-(H1-Pad1.47)") (class "Default")
      (node (ref "H1") (pin "1.47") (pinfunction "1.47_1.47") (pintype "bidirectional"))
    )
    (net (code "115") (name "unconnected-(H1-Pad1.48)") (class "Default")
      (node (ref "H1") (pin "1.48") (pinfunction "1.48_1.48") (pintype "bidirectional"))
    )
    (net (code "116") (name "unconnected-(H1-Pad1.49)") (class "Default")
      (node (ref "H1") (pin "1.49") (pinfunction "1.49_1.49") (pintype "bidirectional"))
    )
    (net (code "117") (name "unconnected-(H1-Pad1.50)") (class "Default")
      (node (ref "H1") (pin "1.50") (pinfunction "1.50_1.50") (pintype "bidirectional"))
    )
    (net (code "118") (name "unconnected-(H1-Pad1.51)") (class "Default")
      (node (ref "H1") (pin "1.51") (pinfunction "1.51_1.51") (pintype "bidirectional"))
    )
    (net (code "119") (name "unconnected-(H1-Pad1.52)") (class "Default")
      (node (ref "H1") (pin "1.52") (pinfunction "1.52_1.52") (pintype "bidirectional"))
    )
    (net (code "120") (name "unconnected-(H1-Pad2.5)") (class "Default")
      (node (ref "H1") (pin "2.5") (pinfunction "2.5_2.5") (pintype "bidirectional"))
    )
    (net (code "121") (name "unconnected-(H1-Pad2.6)") (class "Default")
      (node (ref "H1") (pin "2.6") (pinfunction "2.6_2.6") (pintype "bidirectional"))
    )
    (net (code "122") (name "unconnected-(H1-Pad2.8)") (class "Default")
      (node (ref "H1") (pin "2.8") (pinfunction "2.8_2.8") (pintype "bidirectional"))
    )
    (net (code "123") (name "unconnected-(H1-Pad2.9)") (class "Default")
      (node (ref "H1") (pin "2.9") (pinfunction "2.9_2.9") (pintype "bidirectional"))
    )
    (net (code "124") (name "unconnected-(H1-Pad2.10)") (class "Default")
      (node (ref "H1") (pin "2.10") (pinfunction "2.10_2.10") (pintype "bidirectional"))
    )
    (net (code "125") (name "unconnected-(H1-Pad2.11)") (class "Default")
      (node (ref "H1") (pin "2.11") (pinfunction "2.11_2.11") (pintype "bidirectional"))
    )
    (net (code "126") (name "unconnected-(H1-Pad2.12)") (class "Default")
      (node (ref "H1") (pin "2.12") (pinfunction "2.12_2.12") (pintype "bidirectional"))
    )
    (net (code "127") (name "unconnected-(H1-Pad2.13)") (class "Default")
      (node (ref "H1") (pin "2.13") (pinfunction "2.13_2.13") (pintype "bidirectional"))
    )
    (net (code "128") (name "unconnected-(H1-Pad2.15)") (class "Default")
      (node (ref "H1") (pin "2.15") (pinfunction "2.15_2.15") (pintype "bidirectional"))
    )
    (net (code "129") (name "unconnected-(H1-Pad2.16)") (class "Default")
      (node (ref "H1") (pin "2.16") (pinfunction "2.16_2.16") (pintype "bidirectional"))
    )
    (net (code "130") (name "unconnected-(H1-Pad2.18)") (class "Default")
      (node (ref "H1") (pin "2.18") (pinfunction "2.18_2.18") (pintype "bidirectional"))
    )
    (net (code "131") (name "unconnected-(H1-Pad2.19)") (class "Default")
      (node (ref "H1") (pin "2.19") (pinfunction "2.19_2.19") (pintype "bidirectional"))
    )
    (net (code "132") (name "unconnected-(H1-Pad2.20)") (class "Default")
      (node (ref "H1") (pin "2.20") (pinfunction "2.20_2.20") (pintype "bidirectional"))
    )
    (net (code "133") (name "unconnected-(H1-Pad2.23)") (class "Default")
      (node (ref "H1") (pin "2.23") (pinfunction "2.23_2.23") (pintype "bidirectional"))
    )
    (net (code "134") (name "unconnected-(H1-Pad2.24)") (class "Default")
      (node (ref "H1") (pin "2.24") (pinfunction "2.24_2.24") (pintype "bidirectional"))
    )
    (net (code "135") (name "unconnected-(H1-Pad2.31)") (class "Default")
      (node (ref "H1") (pin "2.31") (pinfunction "2.31_2.31") (pintype "bidirectional"))
    )
    (net (code "136") (name "unconnected-(H1-Pad2.33)") (class "Default")
      (node (ref "H1") (pin "2.33") (pinfunction "2.33_2.33") (pintype "bidirectional"))
    )
    (net (code "137") (name "unconnected-(H1-Pad2.34)") (class "Default")
      (node (ref "H1") (pin "2.34") (pinfunction "2.34_2.34") (pintype "bidirectional"))
    )
    (net (code "138") (name "unconnected-(H1-Pad2.35)") (class "Default")
      (node (ref "H1") (pin "2.35") (pinfunction "2.35_2.35") (pintype "bidirectional"))
    )
    (net (code "139") (name "unconnected-(H1-Pad2.36)") (class "Default")
      (node (ref "H1") (pin "2.36") (pinfunction "2.36_2.36") (pintype "bidirectional"))
    )
    (net (code "140") (name "unconnected-(H1-Pad2.37)") (class "Default")
      (node (ref "H1") (pin "2.37") (pinfunction "2.37_2.37") (pintype "bidirectional"))
    )
    (net (code "141") (name "unconnected-(H1-Pad2.38)") (class "Default")
      (node (ref "H1") (pin "2.38") (pinfunction "2.38_2.38") (pintype "bidirectional"))
    )
    (net (code "142") (name "unconnected-(H1-Pad2.39)") (class "Default")
      (node (ref "H1") (pin "2.39") (pinfunction "2.39_2.39") (pintype "bidirectional"))
    )
    (net (code "143") (name "unconnected-(H1-Pad2.40)") (class "Default")
      (node (ref "H1") (pin "2.40") (pinfunction "2.40_2.40") (pintype "bidirectional"))
    )
    (net (code "144") (name "unconnected-(H1-Pad2.41)") (class "Default")
      (node (ref "H1") (pin "2.41") (pinfunction "2.41_2.41") (pintype "bidirectional"))
    )
    (net (code "145") (name "unconnected-(H1-Pad2.42)") (class "Default")
      (node (ref "H1") (pin "2.42") (pinfunction "2.42_2.42") (pintype "bidirectional"))
    )
    (net (code "146") (name "unconnected-(H1-Pad2.43)") (class "Default")
      (node (ref "H1") (pin "2.43") (pinfunction "2.43_2.43") (pintype "bidirectional"))
    )
    (net (code "147") (name "unconnected-(H1-Pad2.44)") (class "Default")
      (node (ref "H1") (pin "2.44") (pinfunction "2.44_2.44") (pintype "bidirectional"))
    )
    (net (code "148") (name "unconnected-(H1-Pad2.45)") (class "Default")
      (node (ref "H1") (pin "2.45") (pinfunction "2.45_2.45") (pintype "bidirectional"))
    )
    (net (code "149") (name "unconnected-(H1-Pad2.46)") (class "Default")
      (node (ref "H1") (pin "2.46") (pinfunction "2.46_2.46") (pintype "bidirectional"))
    )
    (net (code "150") (name "unconnected-(H1-Pad2.49)") (class "Default")
      (node (ref "H1") (pin "2.49") (pinfunction "2.49_2.49") (pintype "bidirectional"))
    )
    (net (code "151") (name "unconnected-(H1-Pad2.50)") (class "Default")
      (node (ref "H1") (pin "2.50") (pinfunction "2.50_2.50") (pintype "bidirectional"))
    )
    (net (code "152") (name "unconnected-(H1-Pad2.51)") (class "Default")
      (node (ref "H1") (pin "2.51") (pinfunction "2.51_2.51") (pintype "bidirectional"))
    )
    (net (code "153") (name "unconnected-(H1-Pad2.52)") (class "Default")
      (node (ref "H1") (pin "2.52") (pinfunction "2.52_2.52") (pintype "bidirectional"))
    )
    (net (code "154") (name "unconnected-(H1-PadP$1)") (class "Default")
      (node (ref "H1") (pin "P$1") (pinfunction "P$1_P$1") (pintype "bidirectional"))
    )
    (net (code "155") (name "unconnected-(H1-PadP$2)") (class "Default")
      (node (ref "H1") (pin "P$2") (pinfunction "P$2_P$2") (pintype "bidirectional"))
    )
    (net (code "156") (name "unconnected-(H1-PadP$3)") (class "Default")
      (node (ref "H1") (pin "P$3") (pinfunction "P$3_P$3") (pintype "bidirectional"))
    )
    (net (code "157") (name "unconnected-(U$1-Pad40-A16{slash}CS1)") (class "Default")
      (node (ref "U$1") (pin "40-A16/CS1") (pinfunction "40-A16/CS1_40-A16/CS1") (pintype "bidirectional"))
    )
    (net (code "158") (name "unconnected-(U$1-PadON{slash}OFF)") (class "Default")
      (node (ref "U$1") (pin "ON/OFF") (pinfunction "ON/OFF_ON/OFF") (pintype "bidirectional"))
    )
    (net (code "159") (name "unconnected-(U1-NC-Pad7)") (class "Default")
      (node (ref "U1") (pin "7") (pinfunction "NC_7") (pintype "no_connect"))
    )
    (net (code "160") (name "unconnected-(U1-NC_2-Pad2)") (class "Default")
      (node (ref "U1") (pin "2") (pinfunction "NC_2_2") (pintype "no_connect"))
    )
    (net (code "161") (name "unconnected-(U1-NC_3-Pad3)") (class "Default")
      (node (ref "U1") (pin "3") (pinfunction "NC_3_3") (pintype "no_connect"))
    )
    (net (code "162") (name "unconnected-(U1-NC_4-Pad6)") (class "Default")
      (node (ref "U1") (pin "6") (pinfunction "NC_4_6") (pintype "no_connect"))
    )
    (net (code "163") (name "unconnected-(U3-GPIO_2-Pad16)") (class "Default")
      (node (ref "U3") (pin "16") (pinfunction "GPIO_2_16") (pintype "bidirectional"))
    )
    (net (code "164") (name "unconnected-(U4-DIO0-Pad14)") (class "Default")
      (node (ref "U4") (pin "14") (pinfunction "DIO0_14") (pintype "bidirectional"))
    )
    (net (code "165") (name "unconnected-(U4-DIO2-Pad16)") (class "Default")
      (node (ref "U4") (pin "16") (pinfunction "DIO2_16") (pintype "bidirectional"))
    )
    (net (code "166") (name "unconnected-(U4-DIO3-Pad11)") (class "Default")
      (node (ref "U4") (pin "11") (pinfunction "DIO3_11") (pintype "bidirectional"))
    )
    (net (code "167") (name "unconnected-(U4-DIO4-Pad12)") (class "Default")
      (node (ref "U4") (pin "12") (pinfunction "DIO4_12") (pintype "bidirectional"))
    )
    (net (code "168") (name "unconnected-(U4-DIO5-Pad7)") (class "Default")
      (node (ref "U4") (pin "7") (pinfunction "DIO5_7") (pintype "bidirectional"))
    )
    (net (code "169") (name "unconnected-(U5-Pad1)") (class "Default")
      (node (ref "U5") (pin "1") (pinfunction "1_1") (pintype "passive"))
    )
    (net (code "170") (name "unconnected-(U6-P$3-Pad3)") (class "Default")
      (node (ref "U6") (pin "3") (pinfunction "P$3_3") (pintype "bidirectional"))
    )
    (net (code "171") (name "unconnected-(U6-P$4-Pad4)") (class "Default")
      (node (ref "U6") (pin "4") (pinfunction "P$4_4") (pintype "bidirectional"))
    )
    (net (code "172") (name "unconnected-(U6-P$5-Pad5)") (class "Default")
      (node (ref "U6") (pin "5") (pinfunction "P$5_5") (pintype "bidirectional"))
    )
    (net (code "173") (name "unconnected-(U6-P$6-Pad6)") (class "Default")
      (node (ref "U6") (pin "6") (pinfunction "P$6_6") (pintype "bidirectional"))
    )
    (net (code "174") (name "unconnected-(U6-P$8-Pad8)") (class "Default")
      (node (ref "U6") (pin "8") (pinfunction "P$8_8") (pintype "bidirectional"))
    )
    (net (code "175") (name "unconnected-(U6-P$12-Pad12)") (class "Default")
      (node (ref "U6") (pin "12") (pinfunction "P$12_12") (pintype "bidirectional"))
    )
    (net (code "176") (name "unconnected-(U6-P$13-Pad13)") (class "Default")
      (node (ref "U6") (pin "13") (pinfunction "P$13_13") (pintype "bidirectional"))
    )
    (net (code "177") (name "unconnected-(U6-P$14-Pad14)") (class "Default")
      (node (ref "U6") (pin "14") (pinfunction "P$14_14") (pintype "bidirectional"))
    )
    (net (code "178") (name "unconnected-(U6-P$16-Pad16)") (class "Default")
      (node (ref "U6") (pin "16") (pinfunction "P$16_16") (pintype "bidirectional"))
    )
    (net (code "179") (name "unconnected-(U6-P$17-Pad17)") (class "Default")
      (node (ref "U6") (pin "17") (pinfunction "P$17_17") (pintype "bidirectional"))
    )
    (net (code "180") (name "unconnected-(U6-P$20-Pad20)") (class "Default")
      (node (ref "U6") (pin "20") (pinfunction "P$20_20") (pintype "bidirectional"))
    )
    (net (code "181") (name "unconnected-(U6-P$23-Pad23)") (class "Default")
      (node (ref "U6") (pin "23") (pinfunction "P$23_23") (pintype "bidirectional"))
    )
    (net (code "182") (name "unconnected-(U6-P$26-Pad26)") (class "Default")
      (node (ref "U6") (pin "26") (pinfunction "P$26_26") (pintype "bidirectional"))
    )
    (net (code "183") (name "unconnected-(U6-P$30-Pad30)") (class "Default")
      (node (ref "U6") (pin "30") (pinfunction "P$30_30") (pintype "bidirectional"))
    )
    (net (code "184") (name "unconnected-(U6-P$34-Pad34)") (class "Default")
      (node (ref "U6") (pin "34") (pinfunction "P$34_34") (pintype "bidirectional"))
    )
    (net (code "185") (name "unconnected-(U6-P$35-Pad35)") (class "Default")
      (node (ref "U6") (pin "35") (pinfunction "P$35_35") (pintype "bidirectional"))
    )
    (net (code "186") (name "unconnected-(U6-P$36-Pad36)") (class "Default")
      (node (ref "U6") (pin "36") (pinfunction "P$36_36") (pintype "bidirectional"))
    )
    (net (code "187") (name "unconnected-(U6-P$37-Pad37)") (class "Default")
      (node (ref "U6") (pin "37") (pinfunction "P$37_37") (pintype "bidirectional"))
    )
    (net (code "188") (name "unconnected-(U6-P$38-Pad38)") (class "Default")
      (node (ref "U6") (pin "38") (pinfunction "P$38_38") (pintype "bidirectional"))
    )
    (net (code "189") (name "unconnected-(U6-P$39-Pad39)") (class "Default")
      (node (ref "U6") (pin "39") (pinfunction "P$39_39") (pintype "bidirectional"))
    )
    (net (code "190") (name "unconnected-(U6-P$40-Pad40)") (class "Default")
      (node (ref "U6") (pin "40") (pinfunction "P$40_40") (pintype "bidirectional"))
    )
    (net (code "191") (name "unconnected-(U6-P$41-Pad41)") (class "Default")
      (node (ref "U6") (pin "41") (pinfunction "P$41_41") (pintype "bidirectional"))
    )
    (net (code "192") (name "unconnected-(U6-P$43-Pad43)") (class "Default")
      (node (ref "U6") (pin "43") (pinfunction "P$43_43") (pintype "bidirectional"))
    )
    (net (code "193") (name "unconnected-(U6-P$45-Pad45)") (class "Default")
      (node (ref "U6") (pin "45") (pinfunction "P$45_45") (pintype "bidirectional"))
    )
    (net (code "194") (name "unconnected-(U6-P$46-Pad46)") (class "Default")
      (node (ref "U6") (pin "46") (pinfunction "P$46_46") (pintype "bidirectional"))
    )
    (net (code "195") (name "unconnected-(U6-P$47-Pad47)") (class "Default")
      (node (ref "U6") (pin "47") (pinfunction "P$47_47") (pintype "bidirectional"))
    )
    (net (code "196") (name "unconnected-(U6-P$48-Pad48)") (class "Default")
      (node (ref "U6") (pin "48") (pinfunction "P$48_48") (pintype "bidirectional"))
    )
    (net (code "197") (name "unconnected-(U6-P$49-Pad49)") (class "Default")
      (node (ref "U6") (pin "49") (pinfunction "P$49_49") (pintype "bidirectional"))
    )
    (net (code "198") (name "unconnected-(U6-P$50-Pad50)") (class "Default")
      (node (ref "U6") (pin "50") (pinfunction "P$50_50") (pintype "bidirectional"))
    )
    (net (code "199") (name "unconnected-(U6-P$51-Pad51)") (class "Default")
      (node (ref "U6") (pin "51") (pinfunction "P$51_51") (pintype "bidirectional"))
    )
    (net (code "200") (name "unconnected-(U6-P$52-Pad52)") (class "Default")
      (node (ref "U6") (pin "52") (pinfunction "P$52_52") (pintype "bidirectional"))
    )
    (net (code "201") (name "unconnected-(U6-P$53-Pad53)") (class "Default")
      (node (ref "U6") (pin "53") (pinfunction "P$53_53") (pintype "bidirectional"))
    )
    (net (code "202") (name "unconnected-(U6-P$54-Pad54)") (class "Default")
      (node (ref "U6") (pin "54") (pinfunction "P$54_54") (pintype "bidirectional"))
    )
    (net (code "203") (name "unconnected-(U6-P$55-Pad55)") (class "Default")
      (node (ref "U6") (pin "55") (pinfunction "P$55_55") (pintype "bidirectional"))
    )
    (net (code "204") (name "unconnected-(U6-P$56-Pad56)") (class "Default")
      (node (ref "U6") (pin "56") (pinfunction "P$56_56") (pintype "bidirectional"))
    )
    (net (code "205") (name "unconnected-(U6-P$57-Pad57)") (class "Default")
      (node (ref "U6") (pin "57") (pinfunction "P$57_57") (pintype "bidirectional"))
    )
    (net (code "206") (name "unconnected-(U6-P$59-Pad59)") (class "Default")
      (node (ref "U6") (pin "59") (pinfunction "P$59_59") (pintype "bidirectional"))
    )
    (net (code "207") (name "unconnected-(U6-P$60-Pad60)") (class "Default")
      (node (ref "U6") (pin "60") (pinfunction "P$60_60") (pintype "bidirectional"))
    )
    (net (code "208") (name "unconnected-(U6-P$61-Pad61)") (class "Default")
      (node (ref "U6") (pin "61") (pinfunction "P$61_61") (pintype "bidirectional"))
    )
    (net (code "209") (name "unconnected-(U6-P$62-Pad62)") (class "Default")
      (node (ref "U6") (pin "62") (pinfunction "P$62_62") (pintype "bidirectional"))
    )
    (net (code "210") (name "unconnected-(U6-P$63-Pad63)") (class "Default")
      (node (ref "U6") (pin "63") (pinfunction "P$63_63") (pintype "bidirectional"))
    )
    (net (code "211") (name "unconnected-(U6-P$65-Pad65)") (class "Default")
      (node (ref "U6") (pin "65") (pinfunction "P$65_65") (pintype "bidirectional"))
    )
    (net (code "212") (name "unconnected-(U6-P$66-Pad66)") (class "Default")
      (node (ref "U6") (pin "66") (pinfunction "P$66_66") (pintype "bidirectional"))
    )
    (net (code "213") (name "unconnected-(U6-P$67-Pad67)") (class "Default")
      (node (ref "U6") (pin "67") (pinfunction "P$67_67") (pintype "bidirectional"))
    )
    (net (code "214") (name "unconnected-(U6-P$68-Pad68)") (class "Default")
      (node (ref "U6") (pin "68") (pinfunction "P$68_68") (pintype "bidirectional"))
    )
    (net (code "215") (name "unconnected-(U6-P$69-Pad69)") (class "Default")
      (node (ref "U6") (pin "69") (pinfunction "P$69_69") (pintype "bidirectional"))
    )
    (net (code "216") (name "unconnected-(X1-P$1-Pad1)") (class "Default")
      (node (ref "X1") (pin "1") (pinfunction "P$1_1") (pintype "bidirectional"))
    )
    (net (code "217") (name "unconnected-(X1-P$4-Pad4)") (class "Default")
      (node (ref "X1") (pin "4") (pinfunction "P$4_4") (pintype "bidirectional"))
    )
    (net (code "218") (name "unconnected-(X1-P$6-Pad6)") (class "Default")
      (node (ref "X1") (pin "6") (pinfunction "P$6_6") (pintype "bidirectional"))
    )
    (net (code "219") (name "unconnected-(X1-P$7-Pad7)") (class "Default")
      (node (ref "X1") (pin "7") (pinfunction "P$7_7") (pintype "bidirectional"))
    )
    (net (code "220") (name "unconnected-(X1-P$9-Pad9)") (class "Default")
      (node (ref "X1") (pin "9") (pinfunction "P$9_9") (pintype "bidirectional"))
    )
    (net (code "221") (name "unconnected-(X1-P$10-Pad10)") (class "Default")
      (node (ref "X1") (pin "10") (pinfunction "P$10_10") (pintype "bidirectional"))
    )
    (net (code "222") (name "unconnected-(X1-P$12-Pad12)") (class "Default")
      (node (ref "X1") (pin "12") (pinfunction "P$12_12") (pintype "bidirectional"))
    )
    (net (code "223") (name "unconnected-(X1-P$14-Pad14)") (class "Default")
      (node (ref "X1") (pin "14") (pinfunction "P$14_14") (pintype "bidirectional"))
    )
    (net (code "224") (name "unconnected-(X1-P$17-Pad17)") (class "Default")
      (node (ref "X1") (pin "17") (pinfunction "P$17_17") (pintype "bidirectional"))
    )
    (net (code "225") (name "unconnected-(X1-P$20-Pad20)") (class "Default")
      (node (ref "X1") (pin "20") (pinfunction "P$20_20") (pintype "bidirectional"))
    )
    (net (code "226") (name "unconnected-(X1-P$25-Pad25)") (class "Default")
      (node (ref "X1") (pin "25") (pinfunction "P$25_25") (pintype "bidirectional"))
    )
    (net (code "227") (name "unconnected-(X1-P$27-Pad27)") (class "Default")
      (node (ref "X1") (pin "27") (pinfunction "P$27_27") (pintype "bidirectional"))
    )
    (net (code "228") (name "unconnected-(X1-P$28-Pad28)") (class "Default")
      (node (ref "X1") (pin "28") (pinfunction "P$28_28") (pintype "bidirectional"))
    )
    (net (code "229") (name "unconnected-(X1-P$29-Pad29)") (class "Default")
      (node (ref "X1") (pin "29") (pinfunction "P$29_29") (pintype "bidirectional"))
    )
    (net (code "230") (name "unconnected-(X1-P$30-Pad30)") (class "Default")
      (node (ref "X1") (pin "30") (pinfunction "P$30_30") (pintype "bidirectional"))
    )
    (net (code "231") (name "unconnected-(X1-P$31-Pad31)") (class "Default")
      (node (ref "X1") (pin "31") (pinfunction "P$31_31") (pintype "bidirectional"))
    )
    (net (code "232") (name "unconnected-(X1-P$32-Pad32)") (class "Default")
      (node (ref "X1") (pin "32") (pinfunction "P$32_32") (pintype "bidirectional"))
    )
    (net (code "233") (name "unconnected-(X1-P$33-Pad33)") (class "Default")
      (node (ref "X1") (pin "33") (pinfunction "P$33_33") (pintype "bidirectional"))
    )
    (net (code "234") (name "unconnected-(X1-P$34-Pad34)") (class "Default")
      (node (ref "X1") (pin "34") (pinfunction "P$34_34") (pintype "bidirectional"))
    )
    (net (code "235") (name "unconnected-(X1-P$35-Pad35)") (class "Default")
      (node (ref "X1") (pin "35") (pinfunction "P$35_35") (pintype "bidirectional"))
    )
    (net (code "236") (name "unconnected-(X1-P$36-Pad36)") (class "Default")
      (node (ref "X1") (pin "36") (pinfunction "P$36_36") (pintype "bidirectional"))
    )
    (net (code "237") (name "unconnected-(X1-P$37-Pad37)") (class "Default")
      (node (ref "X1") (pin "37") (pinfunction "P$37_37") (pintype "bidirectional"))
    )
    (net (code "238") (name "unconnected-(X1-P$38-Pad38)") (class "Default")
      (node (ref "X1") (pin "38") (pinfunction "P$38_38") (pintype "bidirectional"))
    )
    (net (code "239") (name "unconnected-(X1-P$40-Pad40)") (class "Default")
      (node (ref "X1") (pin "40") (pinfunction "P$40_40") (pintype "bidirectional"))
    )
    (net (code "240") (name "unconnected-(X2-Pad1)") (class "Default")
      (node (ref "X2") (pin "1") (pinfunction "1_1") (pintype "passive"))
    )
    (net (code "241") (name "unconnected-(X2AA-1-Pad33)") (class "Default")
      (node (ref "X2") (pin "33") (pinfunction "1_33") (pintype "passive"))
    )
    (net (code "242") (name "unconnected-(X2AB-1-Pad34)") (class "Default")
      (node (ref "X2") (pin "34") (pinfunction "1_34") (pintype "passive"))
    )
    (net (code "243") (name "unconnected-(X2AC-1-Pad35)") (class "Default")
      (node (ref "X2") (pin "35") (pinfunction "1_35") (pintype "passive"))
    )
    (net (code "244") (name "unconnected-(X2AD-1-Pad36)") (class "Default")
      (node (ref "X2") (pin "36") (pinfunction "1_36") (pintype "passive"))
    )
    (net (code "245") (name "unconnected-(X2AE-1-Pad37)") (class "Default")
      (node (ref "X2") (pin "37") (pinfunction "1_37") (pintype "passive"))
    )
    (net (code "246") (name "unconnected-(X2AF-1-Pad38)") (class "Default")
      (node (ref "X2") (pin "38") (pinfunction "1_38") (pintype "passive"))
    )
    (net (code "247") (name "unconnected-(X2AG-1-Pad39)") (class "Default")
      (node (ref "X2") (pin "39") (pinfunction "1_39") (pintype "passive"))
    )
    (net (code "248") (name "unconnected-(X2AH-1-Pad4)") (class "Default")
      (node (ref "X2") (pin "4") (pinfunction "1_4") (pintype "passive"))
    )
    (net (code "249") (name "unconnected-(X2AI-1-Pad40)") (class "Default")
      (node (ref "X2") (pin "40") (pinfunction "1_40") (pintype "passive"))
    )
    (net (code "250") (name "unconnected-(X2AJ-1-Pad5)") (class "Default")
      (node (ref "X2") (pin "5") (pinfunction "1_5") (pintype "passive"))
    )
    (net (code "251") (name "unconnected-(X2AK-1-Pad6)") (class "Default")
      (node (ref "X2") (pin "6") (pinfunction "1_6") (pintype "passive"))
    )
    (net (code "252") (name "unconnected-(X2AL-1-Pad7)") (class "Default")
      (node (ref "X2") (pin "7") (pinfunction "1_7") (pintype "passive"))
    )
    (net (code "253") (name "unconnected-(X2AM-1-Pad8)") (class "Default")
      (node (ref "X2") (pin "8") (pinfunction "1_8") (pintype "passive"))
    )
    (net (code "254") (name "unconnected-(X2AN-1-Pad9)") (class "Default")
      (node (ref "X2") (pin "9") (pinfunction "1_9") (pintype "passive"))
    )
    (net (code "255") (name "unconnected-(X2B-1-Pad10)") (class "Default")
      (node (ref "X2") (pin "10") (pinfunction "1_10") (pintype "passive"))
    )
    (net (code "256") (name "unconnected-(X2C-1-Pad11)") (class "Default")
      (node (ref "X2") (pin "11") (pinfunction "1_11") (pintype "passive"))
    )
    (net (code "257") (name "unconnected-(X2D-1-Pad12)") (class "Default")
      (node (ref "X2") (pin "12") (pinfunction "1_12") (pintype "passive"))
    )
    (net (code "258") (name "unconnected-(X2E-1-Pad13)") (class "Default")
      (node (ref "X2") (pin "13") (pinfunction "1_13") (pintype "passive"))
    )
    (net (code "259") (name "unconnected-(X2F-1-Pad14)") (class "Default")
      (node (ref "X2") (pin "14") (pinfunction "1_14") (pintype "passive"))
    )
    (net (code "260") (name "unconnected-(X2G-1-Pad15)") (class "Default")
      (node (ref "X2") (pin "15") (pinfunction "1_15") (pintype "passive"))
    )
    (net (code "261") (name "unconnected-(X2H-1-Pad16)") (class "Default")
      (node (ref "X2") (pin "16") (pinfunction "1_16") (pintype "passive"))
    )
    (net (code "262") (name "unconnected-(X2I-1-Pad17)") (class "Default")
      (node (ref "X2") (pin "17") (pinfunction "1_17") (pintype "passive"))
    )
    (net (code "263") (name "unconnected-(X2J-1-Pad18)") (class "Default")
      (node (ref "X2") (pin "18") (pinfunction "1_18") (pintype "passive"))
    )
    (net (code "264") (name "unconnected-(X2K-1-Pad19)") (class "Default")
      (node (ref "X2") (pin "19") (pinfunction "1_19") (pintype "passive"))
    )
    (net (code "265") (name "unconnected-(X2L-1-Pad2)") (class "Default")
      (node (ref "X2") (pin "2") (pinfunction "1_2") (pintype "passive"))
    )
    (net (code "266") (name "unconnected-(X2M-1-Pad20)") (class "Default")
      (node (ref "X2") (pin "20") (pinfunction "1_20") (pintype "passive"))
    )
    (net (code "267") (name "unconnected-(X2N-1-Pad21)") (class "Default")
      (node (ref "X2") (pin "21") (pinfunction "1_21") (pintype "passive"))
    )
    (net (code "268") (name "unconnected-(X2O-1-Pad22)") (class "Default")
      (node (ref "X2") (pin "22") (pinfunction "1_22") (pintype "passive"))
    )
    (net (code "269") (name "unconnected-(X2P-1-Pad23)") (class "Default")
      (node (ref "X2") (pin "23") (pinfunction "1_23") (pintype "passive"))
    )
    (net (code "270") (name "unconnected-(X2Q-1-Pad24)") (class "Default")
      (node (ref "X2") (pin "24") (pinfunction "1_24") (pintype "passive"))
    )
    (net (code "271") (name "unconnected-(X2R-1-Pad25)") (class "Default")
      (node (ref "X2") (pin "25") (pinfunction "1_25") (pintype "passive"))
    )
    (net (code "272") (name "unconnected-(X2S-1-Pad26)") (class "Default")
      (node (ref "X2") (pin "26") (pinfunction "1_26") (pintype "passive"))
    )
    (net (code "273") (name "unconnected-(X2T-1-Pad27)") (class "Default")
      (node (ref "X2") (pin "27") (pinfunction "1_27") (pintype "passive"))
    )
    (net (code "274") (name "unconnected-(X2U-1-Pad28)") (class "Default")
      (node (ref "X2") (pin "28") (pinfunction "1_28") (pintype "passive"))
    )
    (net (code "275") (name "unconnected-(X2V-1-Pad29)") (class "Default")
      (node (ref "X2") (pin "29") (pinfunction "1_29") (pintype "passive"))
    )
    (net (code "276") (name "unconnected-(X2W-1-Pad3)") (class "Default")
      (node (ref "X2") (pin "3") (pinfunction "1_3") (pintype "passive"))
    )
    (net (code "277") (name "unconnected-(X2X-1-Pad30)") (class "Default")
      (node (ref "X2") (pin "30") (pinfunction "1_30") (pintype "passive"))
    )
    (net (code "278") (name "unconnected-(X2Y-1-Pad31)") (class "Default")
      (node (ref "X2") (pin "31") (pinfunction "1_31") (pintype "passive"))
    )
    (net (code "279") (name "unconnected-(X2Z-1-Pad32)") (class "Default")
      (node (ref "X2") (pin "32") (pinfunction "1_32") (pintype "passive"))
    )
  )
)
